# 3PhaseMeter.net
KiCad netlist of a schematic drawn in Altium Designer
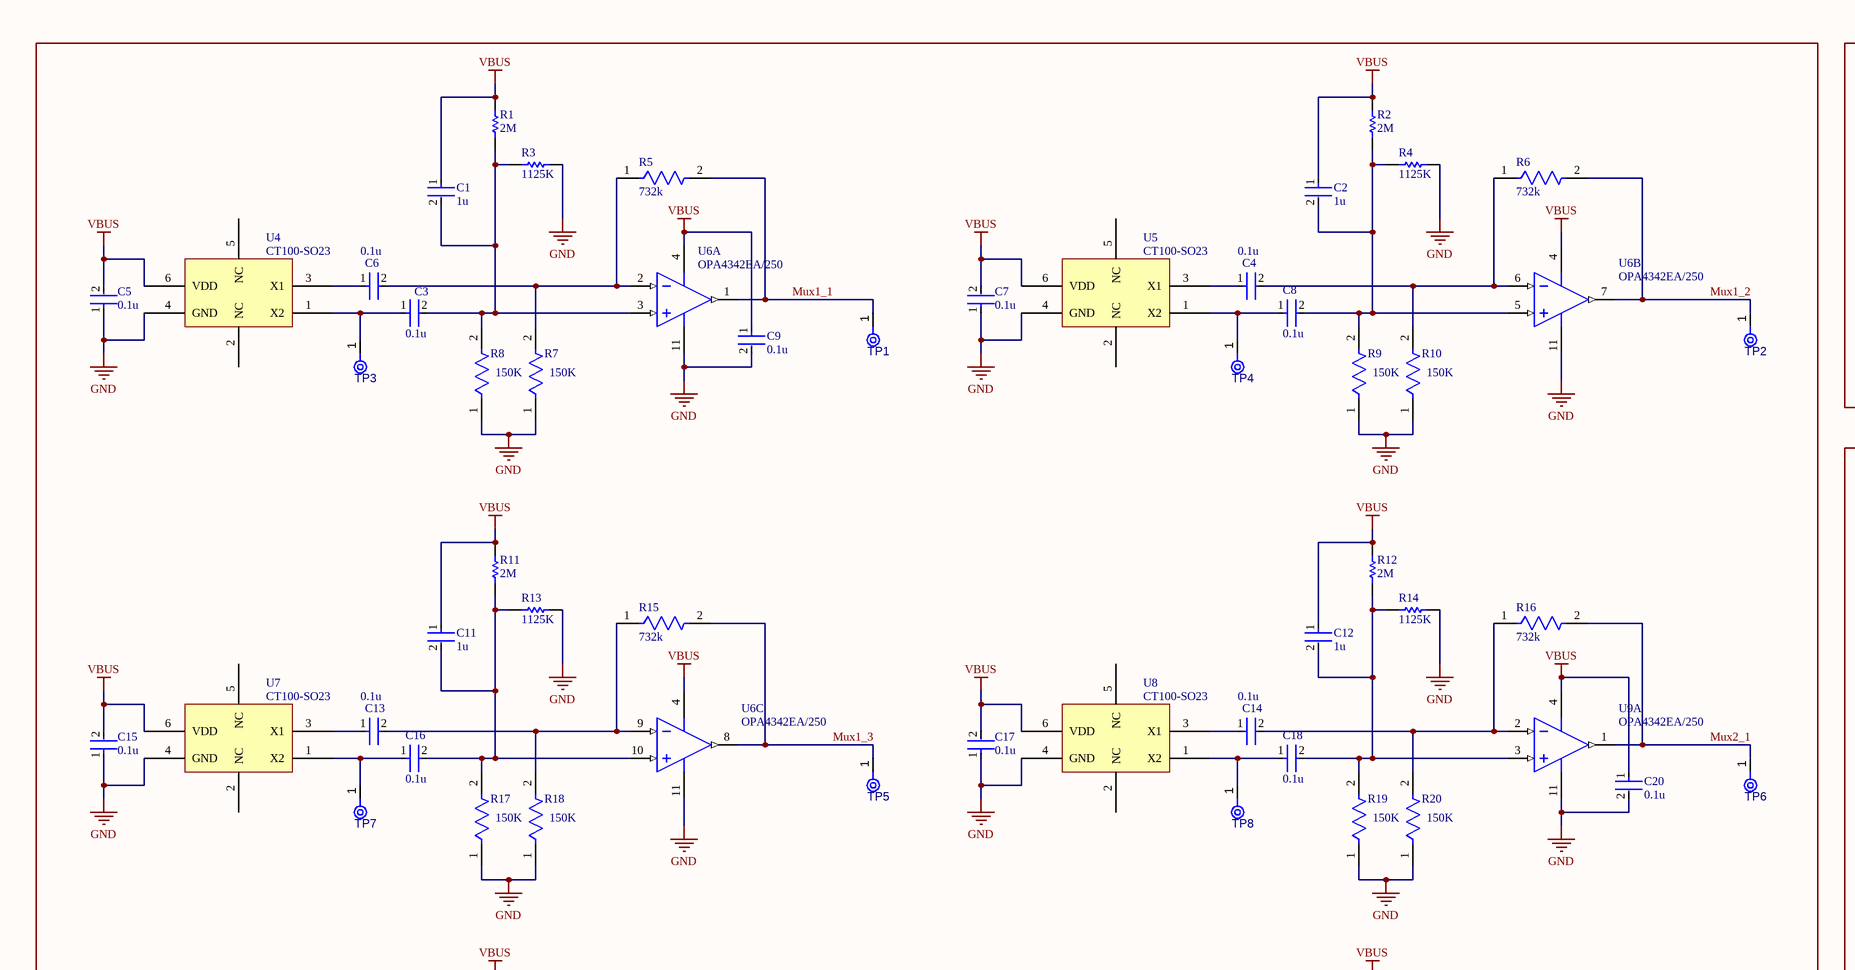
[diagram p0: 3PhaseMeter.SchDoc, top left]
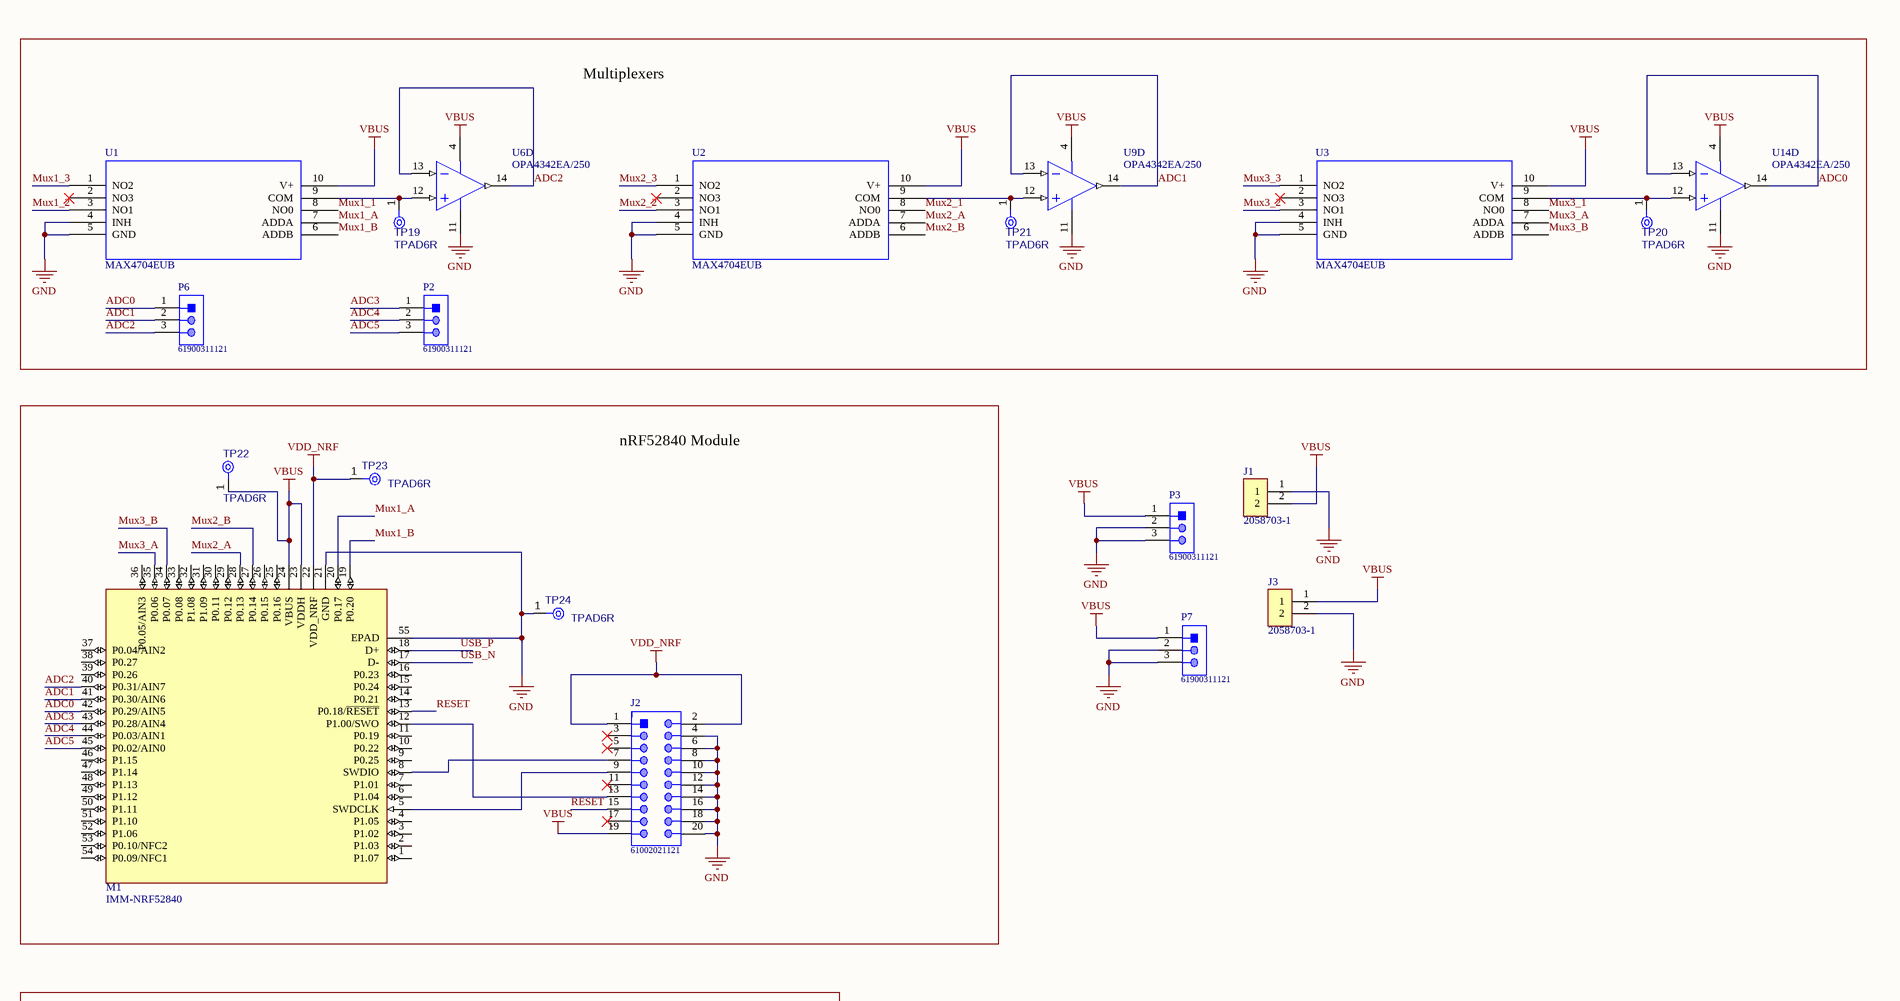
[diagram p1: 3PhaseMeter.SchDoc, top right]
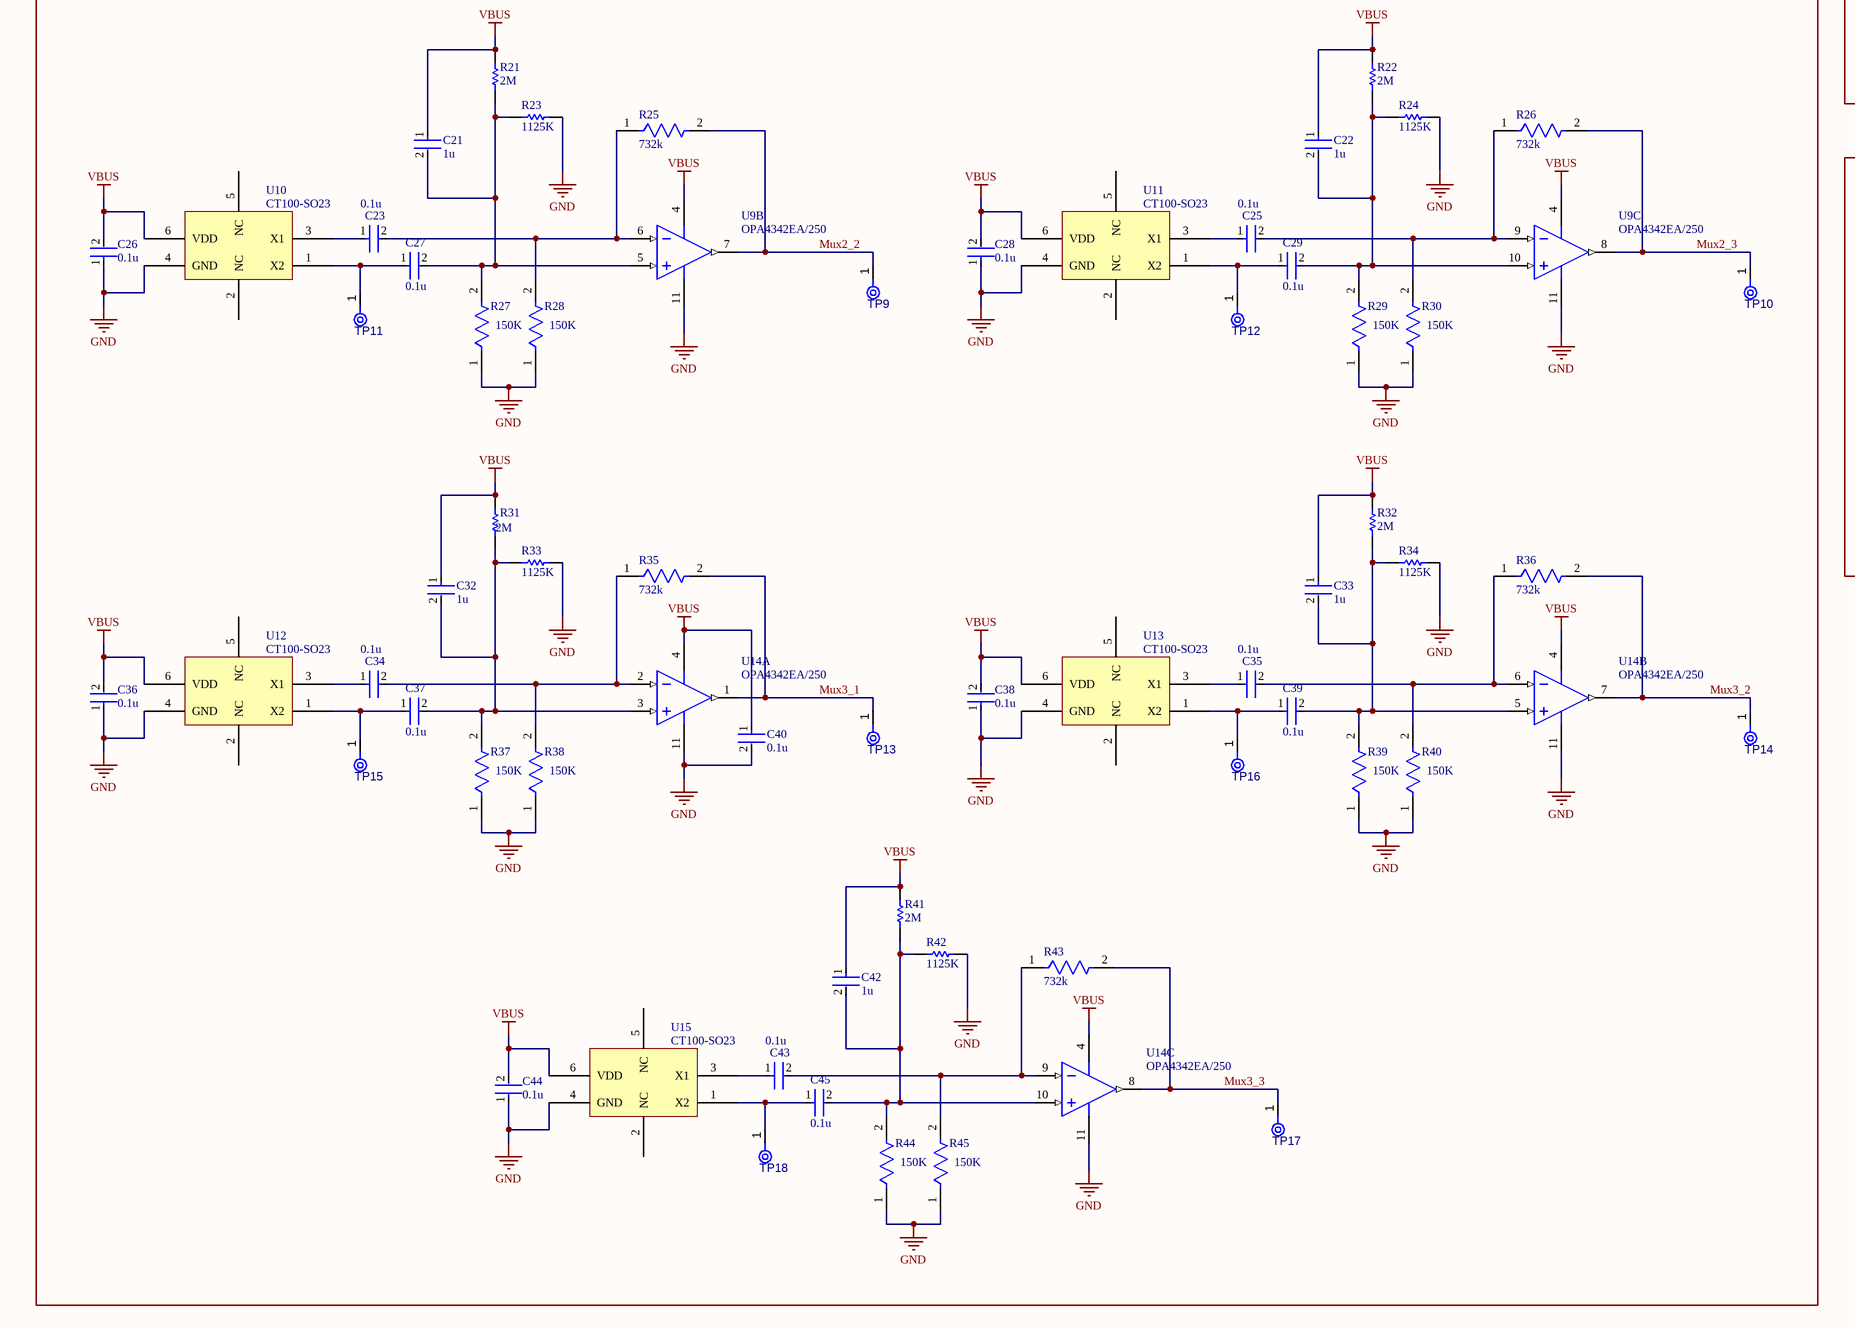
[diagram p2: 3PhaseMeter.SchDoc, bottom left]
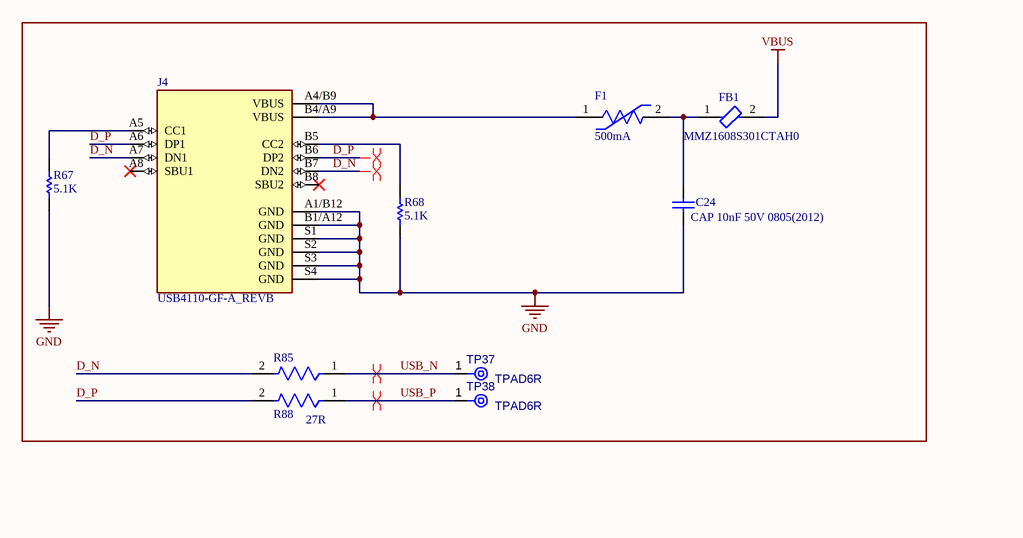
[diagram p3: 3PhaseMeter.SchDoc, bottom right]

(export (version "E")
  (design (tool "Eeschema 10.0.6"))
  (components
    (comp (ref "C1")
      (value "1u")
      (footprint "FP-C3216-160-0_2-IPC_C")
      (description "Multilayer Ceramic Capacitors 1uF ±10% 50V X8R SMD 1206")
      (fields (field (name "TOLERANCE") "10%"))
      (libsource (lib "Altium Content Vault") (part "11868f565c42a9108669ba33697ecf6"))
    )
    (comp (ref "C2")
      (value "1u")
      (footprint "FP-C3216-160-0_2-IPC_C")
      (description "Multilayer Ceramic Capacitors 1uF ±10% 50V X8R SMD 1206")
      (fields (field (name "TOLERANCE") "10%"))
      (libsource (lib "Altium Content Vault") (part "11868f565c42a9108669ba33697ecf6"))
    )
    (comp (ref "C3")
      (value "0.1u")
      (footprint "FP-C0805C-DN-MFG")
      (description "CAP CER 0.1UF 50V X7R 0805")
      (fields
        (field (name "MANUFACTURER PART NUMBER") "C0805C104K5RACTU")
        (field (name "MANUFACTURER") "KEMET")
      )
      (libsource (lib "Altium Content Vault") (part "b4654b650e69147ec39a6b967a45e02"))
    )
    (comp (ref "C4")
      (value "0.1u")
      (footprint "FP-C0805C-DN-MFG")
      (description "CAP CER 0.1UF 50V X7R 0805")
      (fields
        (field (name "MANUFACTURER PART NUMBER") "C0805C104K5RACTU")
        (field (name "MANUFACTURER") "KEMET")
      )
      (libsource (lib "Altium Content Vault") (part "b4654b650e69147ec39a6b967a45e02"))
    )
    (comp (ref "C5")
      (value "0.1u")
      (footprint "FP-C0805C-DN-MFG")
      (description "CAP CER 0.1UF 50V X7R 0805")
      (fields
        (field (name "MANUFACTURER PART NUMBER") "C0805C104K5RACTU")
        (field (name "MANUFACTURER") "KEMET")
      )
      (libsource (lib "Altium Content Vault") (part "b4654b650e69147ec39a6b967a45e02"))
    )
    (comp (ref "C6")
      (value "0.1u")
      (footprint "FP-C0805C-DN-MFG")
      (description "CAP CER 0.1UF 50V X7R 0805")
      (fields
        (field (name "MANUFACTURER PART NUMBER") "C0805C104K5RACTU")
        (field (name "MANUFACTURER") "KEMET")
      )
      (libsource (lib "Altium Content Vault") (part "b4654b650e69147ec39a6b967a45e02"))
    )
    (comp (ref "C7")
      (value "0.1u")
      (footprint "FP-C0805C-DN-MFG")
      (description "CAP CER 0.1UF 50V X7R 0805")
      (fields
        (field (name "MANUFACTURER PART NUMBER") "C0805C104K5RACTU")
        (field (name "MANUFACTURER") "KEMET")
      )
      (libsource (lib "Altium Content Vault") (part "b4654b650e69147ec39a6b967a45e02"))
    )
    (comp (ref "C8")
      (value "0.1u")
      (footprint "FP-C0805C-DN-MFG")
      (description "CAP CER 0.1UF 50V X7R 0805")
      (fields
        (field (name "MANUFACTURER PART NUMBER") "C0805C104K5RACTU")
        (field (name "MANUFACTURER") "KEMET")
      )
      (libsource (lib "Altium Content Vault") (part "b4654b650e69147ec39a6b967a45e02"))
    )
    (comp (ref "C9")
      (value "0.1u")
      (footprint "FP-1206-L_3_2_0_2-W_1_6_0-IPC_A")
      (description "General Purpose Ceramic Capacitor, 1206, 100nF, 5%, X7R, 15%, 50V")
      (fields (field (name "VOLTAGE") "50V") (field (name "TOLERANCE") "5%"))
      (libsource (lib "Altium Content Vault") (part "02cd4be3c70576c341d710602a673aa"))
    )
    (comp (ref "C11")
      (value "1u")
      (footprint "FP-C3216-160-0_2-IPC_C")
      (description "Multilayer Ceramic Capacitors 1uF ±10% 50V X8R SMD 1206")
      (fields (field (name "TOLERANCE") "10%"))
      (libsource (lib "Altium Content Vault") (part "11868f565c42a9108669ba33697ecf6"))
    )
    (comp (ref "C12")
      (value "1u")
      (footprint "FP-C3216-160-0_2-IPC_C")
      (description "Multilayer Ceramic Capacitors 1uF ±10% 50V X8R SMD 1206")
      (fields (field (name "TOLERANCE") "10%"))
      (libsource (lib "Altium Content Vault") (part "11868f565c42a9108669ba33697ecf6"))
    )
    (comp (ref "C13")
      (value "0.1u")
      (footprint "FP-C0805C-DN-MFG")
      (description "CAP CER 0.1UF 50V X7R 0805")
      (fields
        (field (name "MANUFACTURER PART NUMBER") "C0805C104K5RACTU")
        (field (name "MANUFACTURER") "KEMET")
      )
      (libsource (lib "Altium Content Vault") (part "b4654b650e69147ec39a6b967a45e02"))
    )
    (comp (ref "C14")
      (value "0.1u")
      (footprint "FP-C0805C-DN-MFG")
      (description "CAP CER 0.1UF 50V X7R 0805")
      (fields
        (field (name "MANUFACTURER PART NUMBER") "C0805C104K5RACTU")
        (field (name "MANUFACTURER") "KEMET")
      )
      (libsource (lib "Altium Content Vault") (part "b4654b650e69147ec39a6b967a45e02"))
    )
    (comp (ref "C15")
      (value "0.1u")
      (footprint "FP-C0805C-DN-MFG")
      (description "CAP CER 0.1UF 50V X7R 0805")
      (fields
        (field (name "MANUFACTURER PART NUMBER") "C0805C104K5RACTU")
        (field (name "MANUFACTURER") "KEMET")
      )
      (libsource (lib "Altium Content Vault") (part "b4654b650e69147ec39a6b967a45e02"))
    )
    (comp (ref "C16")
      (value "0.1u")
      (footprint "FP-C0805C-DN-MFG")
      (description "CAP CER 0.1UF 50V X7R 0805")
      (fields
        (field (name "MANUFACTURER PART NUMBER") "C0805C104K5RACTU")
        (field (name "MANUFACTURER") "KEMET")
      )
      (libsource (lib "Altium Content Vault") (part "b4654b650e69147ec39a6b967a45e02"))
    )
    (comp (ref "C17")
      (value "0.1u")
      (footprint "FP-C0805C-DN-MFG")
      (description "CAP CER 0.1UF 50V X7R 0805")
      (fields
        (field (name "MANUFACTURER PART NUMBER") "C0805C104K5RACTU")
        (field (name "MANUFACTURER") "KEMET")
      )
      (libsource (lib "Altium Content Vault") (part "b4654b650e69147ec39a6b967a45e02"))
    )
    (comp (ref "C18")
      (value "0.1u")
      (footprint "FP-C0805C-DN-MFG")
      (description "CAP CER 0.1UF 50V X7R 0805")
      (fields
        (field (name "MANUFACTURER PART NUMBER") "C0805C104K5RACTU")
        (field (name "MANUFACTURER") "KEMET")
      )
      (libsource (lib "Altium Content Vault") (part "b4654b650e69147ec39a6b967a45e02"))
    )
    (comp (ref "C20")
      (value "0.1u")
      (footprint "FP-1206-L_3_2_0_2-W_1_6_0-IPC_A")
      (description "General Purpose Ceramic Capacitor, 1206, 100nF, 5%, X7R, 15%, 50V")
      (fields (field (name "VOLTAGE") "50V") (field (name "TOLERANCE") "5%"))
      (libsource (lib "Altium Content Vault") (part "02cd4be3c70576c341d710602a673aa"))
    )
    (comp (ref "C21")
      (value "1u")
      (footprint "FP-C3216-160-0_2-IPC_C")
      (description "Multilayer Ceramic Capacitors 1uF ±10% 50V X8R SMD 1206")
      (fields (field (name "TOLERANCE") "10%"))
      (libsource (lib "Altium Content Vault") (part "11868f565c42a9108669ba33697ecf6"))
    )
    (comp (ref "C22")
      (value "1u")
      (footprint "FP-C3216-160-0_2-IPC_C")
      (description "Multilayer Ceramic Capacitors 1uF ±10% 50V X8R SMD 1206")
      (fields (field (name "TOLERANCE") "10%"))
      (libsource (lib "Altium Content Vault") (part "11868f565c42a9108669ba33697ecf6"))
    )
    (comp (ref "C23")
      (value "0.1u")
      (footprint "FP-C0805C-DN-MFG")
      (description "CAP CER 0.1UF 50V X7R 0805")
      (fields
        (field (name "MANUFACTURER PART NUMBER") "C0805C104K5RACTU")
        (field (name "MANUFACTURER") "KEMET")
      )
      (libsource (lib "Altium Content Vault") (part "b4654b650e69147ec39a6b967a45e02"))
    )
    (comp (ref "C24")
      (value "CAP 10nF 50V 0805(2012)")
      (footprint "CAPC0805(2012)75_N")
      (description "CAP 10nF 50V ±5% 0805 (2012 Metric) Thickness 0.75mm SMD")
      (fields (field (name "TOLERANCE") "Â±5%"))
      (libsource (lib "Altium Content Vault") (part "CAP"))
    )
    (comp (ref "C25")
      (value "0.1u")
      (footprint "FP-C0805C-DN-MFG")
      (description "CAP CER 0.1UF 50V X7R 0805")
      (fields
        (field (name "MANUFACTURER PART NUMBER") "C0805C104K5RACTU")
        (field (name "MANUFACTURER") "KEMET")
      )
      (libsource (lib "Altium Content Vault") (part "b4654b650e69147ec39a6b967a45e02"))
    )
    (comp (ref "C26")
      (value "0.1u")
      (footprint "FP-C0805C-DN-MFG")
      (description "CAP CER 0.1UF 50V X7R 0805")
      (fields
        (field (name "MANUFACTURER PART NUMBER") "C0805C104K5RACTU")
        (field (name "MANUFACTURER") "KEMET")
      )
      (libsource (lib "Altium Content Vault") (part "b4654b650e69147ec39a6b967a45e02"))
    )
    (comp (ref "C27")
      (value "0.1u")
      (footprint "FP-C0805C-DN-MFG")
      (description "CAP CER 0.1UF 50V X7R 0805")
      (fields
        (field (name "MANUFACTURER PART NUMBER") "C0805C104K5RACTU")
        (field (name "MANUFACTURER") "KEMET")
      )
      (libsource (lib "Altium Content Vault") (part "b4654b650e69147ec39a6b967a45e02"))
    )
    (comp (ref "C28")
      (value "0.1u")
      (footprint "FP-C0805C-DN-MFG")
      (description "CAP CER 0.1UF 50V X7R 0805")
      (fields
        (field (name "MANUFACTURER PART NUMBER") "C0805C104K5RACTU")
        (field (name "MANUFACTURER") "KEMET")
      )
      (libsource (lib "Altium Content Vault") (part "b4654b650e69147ec39a6b967a45e02"))
    )
    (comp (ref "C29")
      (value "0.1u")
      (footprint "FP-C0805C-DN-MFG")
      (description "CAP CER 0.1UF 50V X7R 0805")
      (fields
        (field (name "MANUFACTURER PART NUMBER") "C0805C104K5RACTU")
        (field (name "MANUFACTURER") "KEMET")
      )
      (libsource (lib "Altium Content Vault") (part "b4654b650e69147ec39a6b967a45e02"))
    )
    (comp (ref "C32")
      (value "1u")
      (footprint "FP-C3216-160-0_2-IPC_C")
      (description "Multilayer Ceramic Capacitors 1uF ±10% 50V X8R SMD 1206")
      (fields (field (name "TOLERANCE") "10%"))
      (libsource (lib "Altium Content Vault") (part "11868f565c42a9108669ba33697ecf6"))
    )
    (comp (ref "C33")
      (value "1u")
      (footprint "FP-C3216-160-0_2-IPC_C")
      (description "Multilayer Ceramic Capacitors 1uF ±10% 50V X8R SMD 1206")
      (fields (field (name "TOLERANCE") "10%"))
      (libsource (lib "Altium Content Vault") (part "11868f565c42a9108669ba33697ecf6"))
    )
    (comp (ref "C34")
      (value "0.1u")
      (footprint "FP-C0805C-DN-MFG")
      (description "CAP CER 0.1UF 50V X7R 0805")
      (fields
        (field (name "MANUFACTURER PART NUMBER") "C0805C104K5RACTU")
        (field (name "MANUFACTURER") "KEMET")
      )
      (libsource (lib "Altium Content Vault") (part "b4654b650e69147ec39a6b967a45e02"))
    )
    (comp (ref "C35")
      (value "0.1u")
      (footprint "FP-C0805C-DN-MFG")
      (description "CAP CER 0.1UF 50V X7R 0805")
      (fields
        (field (name "MANUFACTURER PART NUMBER") "C0805C104K5RACTU")
        (field (name "MANUFACTURER") "KEMET")
      )
      (libsource (lib "Altium Content Vault") (part "b4654b650e69147ec39a6b967a45e02"))
    )
    (comp (ref "C36")
      (value "0.1u")
      (footprint "FP-C0805C-DN-MFG")
      (description "CAP CER 0.1UF 50V X7R 0805")
      (fields
        (field (name "MANUFACTURER PART NUMBER") "C0805C104K5RACTU")
        (field (name "MANUFACTURER") "KEMET")
      )
      (libsource (lib "Altium Content Vault") (part "b4654b650e69147ec39a6b967a45e02"))
    )
    (comp (ref "C37")
      (value "0.1u")
      (footprint "FP-C0805C-DN-MFG")
      (description "CAP CER 0.1UF 50V X7R 0805")
      (fields
        (field (name "MANUFACTURER PART NUMBER") "C0805C104K5RACTU")
        (field (name "MANUFACTURER") "KEMET")
      )
      (libsource (lib "Altium Content Vault") (part "b4654b650e69147ec39a6b967a45e02"))
    )
    (comp (ref "C38")
      (value "0.1u")
      (footprint "FP-C0805C-DN-MFG")
      (description "CAP CER 0.1UF 50V X7R 0805")
      (fields
        (field (name "MANUFACTURER PART NUMBER") "C0805C104K5RACTU")
        (field (name "MANUFACTURER") "KEMET")
      )
      (libsource (lib "Altium Content Vault") (part "b4654b650e69147ec39a6b967a45e02"))
    )
    (comp (ref "C39")
      (value "0.1u")
      (footprint "FP-C0805C-DN-MFG")
      (description "CAP CER 0.1UF 50V X7R 0805")
      (fields
        (field (name "MANUFACTURER PART NUMBER") "C0805C104K5RACTU")
        (field (name "MANUFACTURER") "KEMET")
      )
      (libsource (lib "Altium Content Vault") (part "b4654b650e69147ec39a6b967a45e02"))
    )
    (comp (ref "C40")
      (value "0.1u")
      (footprint "FP-1206-L_3_2_0_2-W_1_6_0-IPC_A")
      (description "General Purpose Ceramic Capacitor, 1206, 100nF, 5%, X7R, 15%, 50V")
      (fields (field (name "VOLTAGE") "50V") (field (name "TOLERANCE") "5%"))
      (libsource (lib "Altium Content Vault") (part "02cd4be3c70576c341d710602a673aa"))
    )
    (comp (ref "C42")
      (value "1u")
      (footprint "FP-C3216-160-0_2-IPC_C")
      (description "Multilayer Ceramic Capacitors 1uF ±10% 50V X8R SMD 1206")
      (fields (field (name "TOLERANCE") "10%"))
      (libsource (lib "Altium Content Vault") (part "11868f565c42a9108669ba33697ecf6"))
    )
    (comp (ref "C43")
      (value "0.1u")
      (footprint "FP-C0805C-DN-MFG")
      (description "CAP CER 0.1UF 50V X7R 0805")
      (fields
        (field (name "MANUFACTURER PART NUMBER") "C0805C104K5RACTU")
        (field (name "MANUFACTURER") "KEMET")
      )
      (libsource (lib "Altium Content Vault") (part "b4654b650e69147ec39a6b967a45e02"))
    )
    (comp (ref "C44")
      (value "0.1u")
      (footprint "FP-C0805C-DN-MFG")
      (description "CAP CER 0.1UF 50V X7R 0805")
      (fields
        (field (name "MANUFACTURER PART NUMBER") "C0805C104K5RACTU")
        (field (name "MANUFACTURER") "KEMET")
      )
      (libsource (lib "Altium Content Vault") (part "b4654b650e69147ec39a6b967a45e02"))
    )
    (comp (ref "C45")
      (value "0.1u")
      (footprint "FP-C0805C-DN-MFG")
      (description "CAP CER 0.1UF 50V X7R 0805")
      (fields
        (field (name "MANUFACTURER PART NUMBER") "C0805C104K5RACTU")
        (field (name "MANUFACTURER") "KEMET")
      )
      (libsource (lib "Altium Content Vault") (part "b4654b650e69147ec39a6b967a45e02"))
    )
    (comp (ref "F1")
      (value "500mA")
      (footprint "FP-1206L050YR-MFG")
      (description "PTC RESET FUSE 6V 500MA 1206")
      (libsource (lib "Altium Content Vault") (part "fdf083d5f6389a9a1c4e51137f46658"))
    )
    (comp (ref "FB1")
      (value "MMZ1608S301CTAH0")
      (footprint "FP-MMZ1608-0_6-IPC_C")
      (description "Signal Line Ferrite Bead 300 Ω 100MHz 500mA DCR 250mΩ SMD 0603")
      (fields (field (name "TOLERANCE") "25%"))
      (libsource (lib "Altium Content Vault") (part "5f30dd21d616792df468990f7003faa"))
    )
    (comp (ref "J1")
      (value "2058703-1")
      (footprint "TE_2058703-1")
      (description "CONN SSL RCPT & BLADE 2POS 4MM")
      (fields (field (name "MF") "{'manufacturer': u'TE Connectivity'}"))
      (libsource (lib "SnapEDA_Library") (part "2058703-1"))
    )
    (comp (ref "J2")
      (value "61002021121")
      (footprint "61002021121")
      (description "SMT Vertical Pin Header WR-PHD, Pitch 2.54 mm, Dual Row, 20 pins")
      (fields (field (name "MANUFACTURER") "Wurth Elektronik") (field (name "PUBLISHER") "WurthElektronik"))
      (libsource (lib "Altium Content Vault") (part "WE-CN-2P-M-R20"))
    )
    (comp (ref "J3")
      (value "2058703-1")
      (footprint "TE_2058703-1")
      (description "CONN SSL RCPT & BLADE 2POS 4MM")
      (fields (field (name "MF") "{'manufacturer': u'TE Connectivity'}"))
      (libsource (lib "SnapEDA_Library") (part "2058703-1"))
    )
    (comp (ref "J4")
      (value "USB4110-GF-A_REVB")
      (footprint "USB4110-GF-A:GCT_USB4110-GF-A_REVB")
      (fields (field (name "MF") "{'manufacturer': u'GCT'}"))
      (libsource (lib "*") (part "USB4110-GF-A_REVB"))
    )
    (comp (ref "M1")
      (value "IMM-NRF52840")
      (footprint "IMM-NRF52840")
      (description "IMM-NRF52840 - ANT+ & BLE module")
      (libsource (lib "IMM-NRF5x") (part "IMM-NRF52840"))
    )
    (comp (ref "P2")
      (value "61900311121")
      (footprint "61900311121")
      (description "Male Locking Header WR-WTB, THT, Vertical, pitch 2.54 mm, 1 x 3 position")
      (fields (field (name "MANUFACTURER") "Wurth Elektronik") (field (name "PUBLISHER") "WurthElektronik"))
      (libsource (lib "Altium Content Vault") (part "WE-CN-1P-M-R3"))
    )
    (comp (ref "P3")
      (value "61900311121")
      (footprint "61900311121")
      (description "Male Locking Header WR-WTB, THT, Vertical, pitch 2.54 mm, 1 x 3 position")
      (fields (field (name "MANUFACTURER") "Wurth Elektronik") (field (name "PUBLISHER") "WurthElektronik"))
      (libsource (lib "Altium Content Vault") (part "WE-CN-1P-M-R3"))
    )
    (comp (ref "P6")
      (value "61900311121")
      (footprint "61900311121")
      (description "Male Locking Header WR-WTB, THT, Vertical, pitch 2.54 mm, 1 x 3 position")
      (fields (field (name "MANUFACTURER") "Wurth Elektronik") (field (name "PUBLISHER") "WurthElektronik"))
      (libsource (lib "Altium Content Vault") (part "WE-CN-1P-M-R3"))
    )
    (comp (ref "P7")
      (value "61900311121")
      (footprint "61900311121")
      (description "Male Locking Header WR-WTB, THT, Vertical, pitch 2.54 mm, 1 x 3 position")
      (fields (field (name "MANUFACTURER") "Wurth Elektronik") (field (name "PUBLISHER") "WurthElektronik"))
      (libsource (lib "Altium Content Vault") (part "WE-CN-1P-M-R3"))
    )
    (comp (ref "R1")
      (value "2M")
      (footprint "RESC2013X60X40LL20T25")
      (fields (field (name "PART NUMBER") "ERA6AEB204V") (field (name "MANUFACTURER") "Panasonic"))
      (libsource (lib "Altium Content Vault") (part "RES"))
    )
    (comp (ref "R2")
      (value "2M")
      (footprint "RESC2013X60X40LL20T25")
      (fields (field (name "PART NUMBER") "ERA6AEB204V") (field (name "MANUFACTURER") "Panasonic"))
      (libsource (lib "Altium Content Vault") (part "RES"))
    )
    (comp (ref "R3")
      (value "1125K")
      (footprint "RESC2013X60X35ML10T20")
      (description "Chip Resistor, 100 KOhm, +/- 1%, 0.125 W, -55 to 155 degC, 0805 (2012 Metric), RoHS, Tape and Reel")
      (fields (field (name "MANUFACTURER") "Yageo") (field (name "TOLERANCE") "1%"))
      (libsource (lib "Altium Content Vault") (part "RES-2"))
    )
    (comp (ref "R4")
      (value "1125K")
      (footprint "RESC2013X60X35ML10T20")
      (description "Chip Resistor, 100 KOhm, +/- 1%, 0.125 W, -55 to 155 degC, 0805 (2012 Metric), RoHS, Tape and Reel")
      (fields (field (name "MANUFACTURER") "Yageo") (field (name "TOLERANCE") "1%"))
      (libsource (lib "Altium Content Vault") (part "RES-2"))
    )
    (comp (ref "R5")
      (value "732k")
      (footprint "FP-AC0805-MFG")
      (description "Res Thick Film 0805 100K Ohm 1% 1/8W ±100ppm/°C Molded SMD SMD Paper T/R")
      (fields
        (field (name "OCTOPART") "https://octopart.com/ac0805fr-07100kl-yageo-24517275")
        (field (name "MANUFACTURER") "Yageo")
      )
      (libsource (lib "Altium Content Vault") (part "1029c3af85768c4190bb7ad29bc67b5"))
    )
    (comp (ref "R6")
      (value "732k")
      (footprint "FP-AC0805-MFG")
      (description "Res Thick Film 0805 100K Ohm 1% 1/8W ±100ppm/°C Molded SMD SMD Paper T/R")
      (fields
        (field (name "OCTOPART") "https://octopart.com/ac0805fr-07100kl-yageo-24517275")
        (field (name "MANUFACTURER") "Yageo")
      )
      (libsource (lib "Altium Content Vault") (part "1029c3af85768c4190bb7ad29bc67b5"))
    )
    (comp (ref "R7")
      (value "150K")
      (footprint "FP-CRCW0805-e3-MFG")
      (description "RES Thick Film, 150kΩ, 1%, 0.125W, 100ppm/°C, 0805")
      (fields (field (name "TOLERANCE") "1%"))
      (libsource (lib "Altium Content Vault") (part "1029c3af85768c4190bb7ad29bc67b5"))
    )
    (comp (ref "R8")
      (value "150K")
      (footprint "FP-CRCW0805-e3-MFG")
      (description "RES Thick Film, 150kΩ, 1%, 0.125W, 100ppm/°C, 0805")
      (fields (field (name "TOLERANCE") "1%"))
      (libsource (lib "Altium Content Vault") (part "1029c3af85768c4190bb7ad29bc67b5"))
    )
    (comp (ref "R9")
      (value "150K")
      (footprint "FP-CRCW0805-e3-MFG")
      (description "RES Thick Film, 150kΩ, 1%, 0.125W, 100ppm/°C, 0805")
      (fields (field (name "TOLERANCE") "1%"))
      (libsource (lib "Altium Content Vault") (part "1029c3af85768c4190bb7ad29bc67b5"))
    )
    (comp (ref "R10")
      (value "150K")
      (footprint "FP-CRCW0805-e3-MFG")
      (description "RES Thick Film, 150kΩ, 1%, 0.125W, 100ppm/°C, 0805")
      (fields (field (name "TOLERANCE") "1%"))
      (libsource (lib "Altium Content Vault") (part "1029c3af85768c4190bb7ad29bc67b5"))
    )
    (comp (ref "R11")
      (value "2M")
      (footprint "RESC2013X60X40LL20T25")
      (fields (field (name "PART NUMBER") "ERA6AEB204V") (field (name "MANUFACTURER") "Panasonic"))
      (libsource (lib "Altium Content Vault") (part "RES"))
    )
    (comp (ref "R12")
      (value "2M")
      (footprint "RESC2013X60X40LL20T25")
      (fields (field (name "PART NUMBER") "ERA6AEB204V") (field (name "MANUFACTURER") "Panasonic"))
      (libsource (lib "Altium Content Vault") (part "RES"))
    )
    (comp (ref "R13")
      (value "1125K")
      (footprint "RESC2013X60X35ML10T20")
      (description "Chip Resistor, 100 KOhm, +/- 1%, 0.125 W, -55 to 155 degC, 0805 (2012 Metric), RoHS, Tape and Reel")
      (fields (field (name "MANUFACTURER") "Yageo") (field (name "TOLERANCE") "1%"))
      (libsource (lib "Altium Content Vault") (part "RES-2"))
    )
    (comp (ref "R14")
      (value "1125K")
      (footprint "RESC2013X60X35ML10T20")
      (description "Chip Resistor, 100 KOhm, +/- 1%, 0.125 W, -55 to 155 degC, 0805 (2012 Metric), RoHS, Tape and Reel")
      (fields (field (name "MANUFACTURER") "Yageo") (field (name "TOLERANCE") "1%"))
      (libsource (lib "Altium Content Vault") (part "RES-2"))
    )
    (comp (ref "R15")
      (value "732k")
      (footprint "FP-AC0805-MFG")
      (description "Res Thick Film 0805 100K Ohm 1% 1/8W ±100ppm/°C Molded SMD SMD Paper T/R")
      (fields
        (field (name "OCTOPART") "https://octopart.com/ac0805fr-07100kl-yageo-24517275")
        (field (name "MANUFACTURER") "Yageo")
      )
      (libsource (lib "Altium Content Vault") (part "1029c3af85768c4190bb7ad29bc67b5"))
    )
    (comp (ref "R16")
      (value "732k")
      (footprint "FP-AC0805-MFG")
      (description "Res Thick Film 0805 100K Ohm 1% 1/8W ±100ppm/°C Molded SMD SMD Paper T/R")
      (fields
        (field (name "OCTOPART") "https://octopart.com/ac0805fr-07100kl-yageo-24517275")
        (field (name "MANUFACTURER") "Yageo")
      )
      (libsource (lib "Altium Content Vault") (part "1029c3af85768c4190bb7ad29bc67b5"))
    )
    (comp (ref "R17")
      (value "150K")
      (footprint "FP-CRCW0805-e3-MFG")
      (description "RES Thick Film, 150kΩ, 1%, 0.125W, 100ppm/°C, 0805")
      (fields (field (name "TOLERANCE") "1%"))
      (libsource (lib "Altium Content Vault") (part "1029c3af85768c4190bb7ad29bc67b5"))
    )
    (comp (ref "R18")
      (value "150K")
      (footprint "FP-CRCW0805-e3-MFG")
      (description "RES Thick Film, 150kΩ, 1%, 0.125W, 100ppm/°C, 0805")
      (fields (field (name "TOLERANCE") "1%"))
      (libsource (lib "Altium Content Vault") (part "1029c3af85768c4190bb7ad29bc67b5"))
    )
    (comp (ref "R19")
      (value "150K")
      (footprint "FP-CRCW0805-e3-MFG")
      (description "RES Thick Film, 150kΩ, 1%, 0.125W, 100ppm/°C, 0805")
      (fields (field (name "TOLERANCE") "1%"))
      (libsource (lib "Altium Content Vault") (part "1029c3af85768c4190bb7ad29bc67b5"))
    )
    (comp (ref "R20")
      (value "150K")
      (footprint "FP-CRCW0805-e3-MFG")
      (description "RES Thick Film, 150kΩ, 1%, 0.125W, 100ppm/°C, 0805")
      (fields (field (name "TOLERANCE") "1%"))
      (libsource (lib "Altium Content Vault") (part "1029c3af85768c4190bb7ad29bc67b5"))
    )
    (comp (ref "R21")
      (value "2M")
      (footprint "RESC2013X60X40LL20T25")
      (fields (field (name "PART NUMBER") "ERA6AEB204V") (field (name "MANUFACTURER") "Panasonic"))
      (libsource (lib "Altium Content Vault") (part "RES"))
    )
    (comp (ref "R22")
      (value "2M")
      (footprint "RESC2013X60X40LL20T25")
      (fields (field (name "PART NUMBER") "ERA6AEB204V") (field (name "MANUFACTURER") "Panasonic"))
      (libsource (lib "Altium Content Vault") (part "RES"))
    )
    (comp (ref "R23")
      (value "1125K")
      (footprint "RESC2013X60X35ML10T20")
      (description "Chip Resistor, 100 KOhm, +/- 1%, 0.125 W, -55 to 155 degC, 0805 (2012 Metric), RoHS, Tape and Reel")
      (fields (field (name "MANUFACTURER") "Yageo") (field (name "TOLERANCE") "1%"))
      (libsource (lib "Altium Content Vault") (part "RES-2"))
    )
    (comp (ref "R24")
      (value "1125K")
      (footprint "RESC2013X60X35ML10T20")
      (description "Chip Resistor, 100 KOhm, +/- 1%, 0.125 W, -55 to 155 degC, 0805 (2012 Metric), RoHS, Tape and Reel")
      (fields (field (name "MANUFACTURER") "Yageo") (field (name "TOLERANCE") "1%"))
      (libsource (lib "Altium Content Vault") (part "RES-2"))
    )
    (comp (ref "R25")
      (value "732k")
      (footprint "FP-AC0805-MFG")
      (description "Res Thick Film 0805 100K Ohm 1% 1/8W ±100ppm/°C Molded SMD SMD Paper T/R")
      (fields
        (field (name "OCTOPART") "https://octopart.com/ac0805fr-07100kl-yageo-24517275")
        (field (name "MANUFACTURER") "Yageo")
      )
      (libsource (lib "Altium Content Vault") (part "1029c3af85768c4190bb7ad29bc67b5"))
    )
    (comp (ref "R26")
      (value "732k")
      (footprint "FP-AC0805-MFG")
      (description "Res Thick Film 0805 100K Ohm 1% 1/8W ±100ppm/°C Molded SMD SMD Paper T/R")
      (fields
        (field (name "OCTOPART") "https://octopart.com/ac0805fr-07100kl-yageo-24517275")
        (field (name "MANUFACTURER") "Yageo")
      )
      (libsource (lib "Altium Content Vault") (part "1029c3af85768c4190bb7ad29bc67b5"))
    )
    (comp (ref "R27")
      (value "150K")
      (footprint "FP-CRCW0805-e3-MFG")
      (description "RES Thick Film, 150kΩ, 1%, 0.125W, 100ppm/°C, 0805")
      (fields (field (name "TOLERANCE") "1%"))
      (libsource (lib "Altium Content Vault") (part "1029c3af85768c4190bb7ad29bc67b5"))
    )
    (comp (ref "R28")
      (value "150K")
      (footprint "FP-CRCW0805-e3-MFG")
      (description "RES Thick Film, 150kΩ, 1%, 0.125W, 100ppm/°C, 0805")
      (fields (field (name "TOLERANCE") "1%"))
      (libsource (lib "Altium Content Vault") (part "1029c3af85768c4190bb7ad29bc67b5"))
    )
    (comp (ref "R29")
      (value "150K")
      (footprint "FP-CRCW0805-e3-MFG")
      (description "RES Thick Film, 150kΩ, 1%, 0.125W, 100ppm/°C, 0805")
      (fields (field (name "TOLERANCE") "1%"))
      (libsource (lib "Altium Content Vault") (part "1029c3af85768c4190bb7ad29bc67b5"))
    )
    (comp (ref "R30")
      (value "150K")
      (footprint "FP-CRCW0805-e3-MFG")
      (description "RES Thick Film, 150kΩ, 1%, 0.125W, 100ppm/°C, 0805")
      (fields (field (name "TOLERANCE") "1%"))
      (libsource (lib "Altium Content Vault") (part "1029c3af85768c4190bb7ad29bc67b5"))
    )
    (comp (ref "R31")
      (value "2M")
      (footprint "RESC2013X60X40LL20T25")
      (fields (field (name "PART NUMBER") "ERA6AEB204V") (field (name "MANUFACTURER") "Panasonic"))
      (libsource (lib "Altium Content Vault") (part "RES"))
    )
    (comp (ref "R32")
      (value "2M")
      (footprint "RESC2013X60X40LL20T25")
      (fields (field (name "PART NUMBER") "ERA6AEB204V") (field (name "MANUFACTURER") "Panasonic"))
      (libsource (lib "Altium Content Vault") (part "RES"))
    )
    (comp (ref "R33")
      (value "1125K")
      (footprint "RESC2013X60X35ML10T20")
      (description "Chip Resistor, 100 KOhm, +/- 1%, 0.125 W, -55 to 155 degC, 0805 (2012 Metric), RoHS, Tape and Reel")
      (fields (field (name "MANUFACTURER") "Yageo") (field (name "TOLERANCE") "1%"))
      (libsource (lib "Altium Content Vault") (part "RES-2"))
    )
    (comp (ref "R34")
      (value "1125K")
      (footprint "RESC2013X60X35ML10T20")
      (description "Chip Resistor, 100 KOhm, +/- 1%, 0.125 W, -55 to 155 degC, 0805 (2012 Metric), RoHS, Tape and Reel")
      (fields (field (name "MANUFACTURER") "Yageo") (field (name "TOLERANCE") "1%"))
      (libsource (lib "Altium Content Vault") (part "RES-2"))
    )
    (comp (ref "R35")
      (value "732k")
      (footprint "FP-AC0805-MFG")
      (description "Res Thick Film 0805 100K Ohm 1% 1/8W ±100ppm/°C Molded SMD SMD Paper T/R")
      (fields
        (field (name "OCTOPART") "https://octopart.com/ac0805fr-07100kl-yageo-24517275")
        (field (name "MANUFACTURER") "Yageo")
      )
      (libsource (lib "Altium Content Vault") (part "1029c3af85768c4190bb7ad29bc67b5"))
    )
    (comp (ref "R36")
      (value "732k")
      (footprint "FP-AC0805-MFG")
      (description "Res Thick Film 0805 100K Ohm 1% 1/8W ±100ppm/°C Molded SMD SMD Paper T/R")
      (fields
        (field (name "OCTOPART") "https://octopart.com/ac0805fr-07100kl-yageo-24517275")
        (field (name "MANUFACTURER") "Yageo")
      )
      (libsource (lib "Altium Content Vault") (part "1029c3af85768c4190bb7ad29bc67b5"))
    )
    (comp (ref "R37")
      (value "150K")
      (footprint "FP-CRCW0805-e3-MFG")
      (description "RES Thick Film, 150kΩ, 1%, 0.125W, 100ppm/°C, 0805")
      (fields (field (name "TOLERANCE") "1%"))
      (libsource (lib "Altium Content Vault") (part "1029c3af85768c4190bb7ad29bc67b5"))
    )
    (comp (ref "R38")
      (value "150K")
      (footprint "FP-CRCW0805-e3-MFG")
      (description "RES Thick Film, 150kΩ, 1%, 0.125W, 100ppm/°C, 0805")
      (fields (field (name "TOLERANCE") "1%"))
      (libsource (lib "Altium Content Vault") (part "1029c3af85768c4190bb7ad29bc67b5"))
    )
    (comp (ref "R39")
      (value "150K")
      (footprint "FP-CRCW0805-e3-MFG")
      (description "RES Thick Film, 150kΩ, 1%, 0.125W, 100ppm/°C, 0805")
      (fields (field (name "TOLERANCE") "1%"))
      (libsource (lib "Altium Content Vault") (part "1029c3af85768c4190bb7ad29bc67b5"))
    )
    (comp (ref "R40")
      (value "150K")
      (footprint "FP-CRCW0805-e3-MFG")
      (description "RES Thick Film, 150kΩ, 1%, 0.125W, 100ppm/°C, 0805")
      (fields (field (name "TOLERANCE") "1%"))
      (libsource (lib "Altium Content Vault") (part "1029c3af85768c4190bb7ad29bc67b5"))
    )
    (comp (ref "R41")
      (value "2M")
      (footprint "RESC2013X60X40LL20T25")
      (fields (field (name "PART NUMBER") "ERA6AEB204V") (field (name "MANUFACTURER") "Panasonic"))
      (libsource (lib "Altium Content Vault") (part "RES"))
    )
    (comp (ref "R42")
      (value "1125K")
      (footprint "RESC2013X60X35ML10T20")
      (description "Chip Resistor, 100 KOhm, +/- 1%, 0.125 W, -55 to 155 degC, 0805 (2012 Metric), RoHS, Tape and Reel")
      (fields (field (name "MANUFACTURER") "Yageo") (field (name "TOLERANCE") "1%"))
      (libsource (lib "Altium Content Vault") (part "RES-2"))
    )
    (comp (ref "R43")
      (value "732k")
      (footprint "FP-AC0805-MFG")
      (description "Res Thick Film 0805 100K Ohm 1% 1/8W ±100ppm/°C Molded SMD SMD Paper T/R")
      (fields
        (field (name "OCTOPART") "https://octopart.com/ac0805fr-07100kl-yageo-24517275")
        (field (name "MANUFACTURER") "Yageo")
      )
      (libsource (lib "Altium Content Vault") (part "1029c3af85768c4190bb7ad29bc67b5"))
    )
    (comp (ref "R44")
      (value "150K")
      (footprint "FP-CRCW0805-e3-MFG")
      (description "RES Thick Film, 150kΩ, 1%, 0.125W, 100ppm/°C, 0805")
      (fields (field (name "TOLERANCE") "1%"))
      (libsource (lib "Altium Content Vault") (part "1029c3af85768c4190bb7ad29bc67b5"))
    )
    (comp (ref "R45")
      (value "150K")
      (footprint "FP-CRCW0805-e3-MFG")
      (description "RES Thick Film, 150kΩ, 1%, 0.125W, 100ppm/°C, 0805")
      (fields (field (name "TOLERANCE") "1%"))
      (libsource (lib "Altium Content Vault") (part "1029c3af85768c4190bb7ad29bc67b5"))
    )
    (comp (ref "R67")
      (value "5.1K")
      (footprint "RESC2013X70X40LL20T20")
      (fields (field (name "PART NUMBER") "ERJ6ENF5101V") (field (name "MANUFACTURER") "Panasonic"))
      (libsource (lib "Altium Content Vault") (part "RES"))
    )
    (comp (ref "R68")
      (value "5.1K")
      (footprint "RESC2013X70X40LL20T20")
      (fields (field (name "PART NUMBER") "ERJ6ENF5101V") (field (name "MANUFACTURER") "Panasonic"))
      (libsource (lib "Altium Content Vault") (part "RES"))
    )
    (comp (ref "R85")
      (value "27R")
      (footprint "FP-CRCW0805-e3-IPC_B")
      (description "RES Thick Film, 27Ω, 1%, 0.125W, 100ppm/°C, 0805")
      (fields (field (name "TOLERANCE") "1%"))
      (libsource (lib "Altium Content Vault") (part "1029c3af85768c4190bb7ad29bc67b5"))
    )
    (comp (ref "R88")
      (value "CRCW080527R0FKEA")
      (footprint "FP-CRCW0805-e3-IPC_B")
      (description "RES Thick Film, 27Ω, 1%, 0.125W, 100ppm/°C, 0805")
      (fields (field (name "TOLERANCE") "1%"))
      (libsource (lib "Altium Content Vault") (part "1029c3af85768c4190bb7ad29bc67b5"))
    )
    (comp (ref "TP1")
      (value "TPAD6R")
      (footprint "TP06R")
      (description "0.6mm round")
      (libsource (lib "Irfaan's Workspace") (part "CMP-001-0001-4"))
    )
    (comp (ref "TP2")
      (value "TPAD6R")
      (footprint "TP06R")
      (description "0.6mm round")
      (libsource (lib "Irfaan's Workspace") (part "CMP-001-0001-4"))
    )
    (comp (ref "TP3")
      (value "TPAD6R")
      (footprint "TP06R")
      (description "0.6mm round")
      (libsource (lib "Irfaan's Workspace") (part "CMP-001-0001-4"))
    )
    (comp (ref "TP4")
      (value "TPAD6R")
      (footprint "TP06R")
      (description "0.6mm round")
      (libsource (lib "Irfaan's Workspace") (part "CMP-001-0001-4"))
    )
    (comp (ref "TP5")
      (value "TPAD6R")
      (footprint "TP06R")
      (description "0.6mm round")
      (libsource (lib "Irfaan's Workspace") (part "CMP-001-0001-4"))
    )
    (comp (ref "TP6")
      (value "TPAD6R")
      (footprint "TP06R")
      (description "0.6mm round")
      (libsource (lib "Irfaan's Workspace") (part "CMP-001-0001-4"))
    )
    (comp (ref "TP7")
      (value "TPAD6R")
      (footprint "TP06R")
      (description "0.6mm round")
      (libsource (lib "Irfaan's Workspace") (part "CMP-001-0001-4"))
    )
    (comp (ref "TP8")
      (value "TPAD6R")
      (footprint "TP06R")
      (description "0.6mm round")
      (libsource (lib "Irfaan's Workspace") (part "CMP-001-0001-4"))
    )
    (comp (ref "TP9")
      (value "TPAD6R")
      (footprint "TP06R")
      (description "0.6mm round")
      (libsource (lib "Irfaan's Workspace") (part "CMP-001-0001-4"))
    )
    (comp (ref "TP10")
      (value "TPAD6R")
      (footprint "TP06R")
      (description "0.6mm round")
      (libsource (lib "Irfaan's Workspace") (part "CMP-001-0001-4"))
    )
    (comp (ref "TP11")
      (value "TPAD6R")
      (footprint "TP06R")
      (description "0.6mm round")
      (libsource (lib "Irfaan's Workspace") (part "CMP-001-0001-4"))
    )
    (comp (ref "TP12")
      (value "TPAD6R")
      (footprint "TP06R")
      (description "0.6mm round")
      (libsource (lib "Irfaan's Workspace") (part "CMP-001-0001-4"))
    )
    (comp (ref "TP13")
      (value "TPAD6R")
      (footprint "TP06R")
      (description "0.6mm round")
      (libsource (lib "Irfaan's Workspace") (part "CMP-001-0001-4"))
    )
    (comp (ref "TP14")
      (value "TPAD6R")
      (footprint "TP06R")
      (description "0.6mm round")
      (libsource (lib "Irfaan's Workspace") (part "CMP-001-0001-4"))
    )
    (comp (ref "TP15")
      (value "TPAD6R")
      (footprint "TP06R")
      (description "0.6mm round")
      (libsource (lib "Irfaan's Workspace") (part "CMP-001-0001-4"))
    )
    (comp (ref "TP16")
      (value "TPAD6R")
      (footprint "TP06R")
      (description "0.6mm round")
      (libsource (lib "Irfaan's Workspace") (part "CMP-001-0001-4"))
    )
    (comp (ref "TP17")
      (value "TPAD6R")
      (footprint "TP06R")
      (description "0.6mm round")
      (libsource (lib "Irfaan's Workspace") (part "CMP-001-0001-4"))
    )
    (comp (ref "TP18")
      (value "TPAD6R")
      (footprint "TP06R")
      (description "0.6mm round")
      (libsource (lib "Irfaan's Workspace") (part "CMP-001-0001-4"))
    )
    (comp (ref "TP19")
      (value "TPAD6R")
      (footprint "TP06R")
      (description "0.6mm round")
      (libsource (lib "Irfaan's Workspace") (part "CMP-001-0001-4"))
    )
    (comp (ref "TP20")
      (value "TPAD6R")
      (footprint "TP06R")
      (description "0.6mm round")
      (libsource (lib "Irfaan's Workspace") (part "CMP-001-0001-4"))
    )
    (comp (ref "TP21")
      (value "TPAD6R")
      (footprint "TP06R")
      (description "0.6mm round")
      (libsource (lib "Irfaan's Workspace") (part "CMP-001-0001-4"))
    )
    (comp (ref "TP22")
      (value "TPAD6R")
      (footprint "TP06R")
      (description "0.6mm round")
      (libsource (lib "Irfaan's Workspace") (part "CMP-001-0001-4"))
    )
    (comp (ref "TP23")
      (value "TPAD6R")
      (footprint "TP06R")
      (description "0.6mm round")
      (libsource (lib "Irfaan's Workspace") (part "CMP-001-0001-4"))
    )
    (comp (ref "TP24")
      (value "TPAD6R")
      (footprint "TP06R")
      (description "0.6mm round")
      (libsource (lib "Irfaan's Workspace") (part "CMP-001-0001-4"))
    )
    (comp (ref "TP37")
      (value "TPAD6R")
      (footprint "TP06R")
      (description "0.6mm round")
      (libsource (lib "Irfaan's Workspace") (part "CMP-001-0001-4"))
    )
    (comp (ref "TP38")
      (value "TPAD6R")
      (footprint "TP06R")
      (description "0.6mm round")
      (libsource (lib "Irfaan's Workspace") (part "CMP-001-0001-4"))
    )
    (comp (ref "U1")
      (value "MAX4704EUB")
      (footprint "21-0061L")
      (fields (field (name "MF") "{'manufacturer': u'Maxim Integrated'}"))
      (libsource (lib "SnapEDA_Library") (part "MAX4704EUB"))
    )
    (comp (ref "U2")
      (value "MAX4704EUB")
      (footprint "21-0061L")
      (fields (field (name "MF") "{'manufacturer': u'Maxim Integrated'}"))
      (libsource (lib "SnapEDA_Library") (part "MAX4704EUB"))
    )
    (comp (ref "U3")
      (value "MAX4704EUB")
      (footprint "21-0061L")
      (fields (field (name "MF") "{'manufacturer': u'Maxim Integrated'}"))
      (libsource (lib "SnapEDA_Library") (part "MAX4704EUB"))
    )
    (comp (ref "U4")
      (value "CT100-SO23")
      (footprint "SOT95P280X135-6N")
      (description "TMR Sensor")
      (libsource (lib "Irfaan's Workspace") (part "CT100-SO23-Symbol-1"))
    )
    (comp (ref "U5")
      (value "CT100-SO23")
      (footprint "SOT95P280X135-6N")
      (description "TMR Sensor")
      (libsource (lib "Irfaan's Workspace") (part "CT100-SO23-Symbol-1"))
    )
    (comp (ref "U6")
      (value "OPA4342EA/250")
      (footprint "PW0014A_M")
      (fields (field (name "MANUFACTURER") "Texas Instruments"))
      (libsource (lib "Altium Content Vault") (part "TI-OPA16X4_4XXX-14"))
    )
    (comp (ref "U7")
      (value "CT100-SO23")
      (footprint "SOT95P280X135-6N")
      (description "TMR Sensor")
      (libsource (lib "Irfaan's Workspace") (part "CT100-SO23-Symbol-1"))
    )
    (comp (ref "U8")
      (value "CT100-SO23")
      (footprint "SOT95P280X135-6N")
      (description "TMR Sensor")
      (libsource (lib "Irfaan's Workspace") (part "CT100-SO23-Symbol-1"))
    )
    (comp (ref "U9")
      (value "OPA4342EA/250")
      (footprint "PW0014A_M")
      (fields (field (name "MANUFACTURER") "Texas Instruments"))
      (libsource (lib "Altium Content Vault") (part "TI-OPA16X4_4XXX-14"))
    )
    (comp (ref "U10")
      (value "CT100-SO23")
      (footprint "SOT95P280X135-6N")
      (description "TMR Sensor")
      (libsource (lib "Irfaan's Workspace") (part "CT100-SO23-Symbol-1"))
    )
    (comp (ref "U11")
      (value "CT100-SO23")
      (footprint "SOT95P280X135-6N")
      (description "TMR Sensor")
      (libsource (lib "Irfaan's Workspace") (part "CT100-SO23-Symbol-1"))
    )
    (comp (ref "U12")
      (value "CT100-SO23")
      (footprint "SOT95P280X135-6N")
      (description "TMR Sensor")
      (libsource (lib "Irfaan's Workspace") (part "CT100-SO23-Symbol-1"))
    )
    (comp (ref "U13")
      (value "CT100-SO23")
      (footprint "SOT95P280X135-6N")
      (description "TMR Sensor")
      (libsource (lib "Irfaan's Workspace") (part "CT100-SO23-Symbol-1"))
    )
    (comp (ref "U14")
      (value "OPA4342EA/250")
      (footprint "PW0014A_M")
      (fields (field (name "MANUFACTURER") "Texas Instruments"))
      (libsource (lib "Altium Content Vault") (part "TI-OPA16X4_4XXX-14"))
    )
    (comp (ref "U15")
      (value "CT100-SO23")
      (footprint "SOT95P280X135-6N")
      (description "TMR Sensor")
      (libsource (lib "Irfaan's Workspace") (part "CT100-SO23-Symbol-1"))
    )
  )
  (nets
    (net (code "1") (name "/ADC0") (class "Default")
      (node (ref "M1") (pin "42") (pinfunction "P0.29/AIN5_42") (pintype "bidirectional"))
      (node (ref "P6") (pin "1") (pinfunction "1_1") (pintype "passive"))
      (node (ref "U14") (pin "13") (pinfunction "IN_D-_13") (pintype "input"))
      (node (ref "U14") (pin "14") (pinfunction "OUT_D_14") (pintype "output"))
    )
    (net (code "2") (name "/ADC1") (class "Default")
      (node (ref "M1") (pin "41") (pinfunction "P0.30/AIN6_41") (pintype "bidirectional"))
      (node (ref "P6") (pin "2") (pinfunction "2_2") (pintype "passive"))
      (node (ref "U9") (pin "13") (pinfunction "IN_D-_13") (pintype "input"))
      (node (ref "U9") (pin "14") (pinfunction "OUT_D_14") (pintype "output"))
    )
    (net (code "3") (name "/ADC2") (class "Default")
      (node (ref "M1") (pin "40") (pinfunction "P0.31/AIN7_40") (pintype "bidirectional"))
      (node (ref "P6") (pin "3") (pinfunction "3_3") (pintype "passive"))
      (node (ref "U6") (pin "13") (pinfunction "IN_D-_13") (pintype "input"))
      (node (ref "U6") (pin "14") (pinfunction "OUT_D_14") (pintype "output"))
    )
    (net (code "4") (name "/ADC3") (class "Default")
      (node (ref "M1") (pin "43") (pinfunction "P0.28/AIN4_43") (pintype "bidirectional"))
      (node (ref "P2") (pin "1") (pinfunction "1_1") (pintype "passive"))
    )
    (net (code "5") (name "/ADC4") (class "Default")
      (node (ref "M1") (pin "44") (pinfunction "P0.03/AIN1_44") (pintype "bidirectional"))
      (node (ref "P2") (pin "2") (pinfunction "2_2") (pintype "passive"))
    )
    (net (code "6") (name "/ADC5") (class "Default")
      (node (ref "M1") (pin "45") (pinfunction "P0.02/AIN0_45") (pintype "bidirectional"))
      (node (ref "P2") (pin "3") (pinfunction "3_3") (pintype "passive"))
    )
    (net (code "7") (name "/D_N") (class "Default")
      (node (ref "J4") (pin "A7") (pinfunction "DN1_A7") (pintype "bidirectional"))
      (node (ref "J4") (pin "B7") (pinfunction "DN2_B7") (pintype "bidirectional"))
      (node (ref "R85") (pin "2") (pinfunction "2_2") (pintype "passive"))
    )
    (net (code "8") (name "/D_P") (class "Default")
      (node (ref "J4") (pin "A6") (pinfunction "DP1_A6") (pintype "bidirectional"))
      (node (ref "J4") (pin "B6") (pinfunction "DP2_B6") (pintype "bidirectional"))
      (node (ref "R88") (pin "2") (pinfunction "2_2") (pintype "passive"))
    )
    (net (code "9") (name "/Mux1_1") (class "Default")
      (node (ref "R5") (pin "2") (pinfunction "2_2") (pintype "passive"))
      (node (ref "TP1") (pin "1") (pinfunction "TP_1") (pintype "passive"))
      (node (ref "U1") (pin "8") (pinfunction "NO0_8") (pintype "passive"))
      (node (ref "U6") (pin "1") (pinfunction "OUT_A_1") (pintype "output"))
    )
    (net (code "10") (name "/Mux1_2") (class "Default")
      (node (ref "R6") (pin "2") (pinfunction "2_2") (pintype "passive"))
      (node (ref "TP2") (pin "1") (pinfunction "TP_1") (pintype "passive"))
      (node (ref "U1") (pin "3") (pinfunction "NO1_3") (pintype "passive"))
      (node (ref "U6") (pin "7") (pinfunction "OUT_B_7") (pintype "output"))
    )
    (net (code "11") (name "/Mux1_3") (class "Default")
      (node (ref "R15") (pin "2") (pinfunction "2_2") (pintype "passive"))
      (node (ref "TP5") (pin "1") (pinfunction "TP_1") (pintype "passive"))
      (node (ref "U1") (pin "1") (pinfunction "NO2_1") (pintype "passive"))
      (node (ref "U6") (pin "8") (pinfunction "OUT_C_8") (pintype "output"))
    )
    (net (code "12") (name "/Mux1_A") (class "Default")
      (node (ref "M1") (pin "20") (pinfunction "P0.17_20") (pintype "bidirectional"))
      (node (ref "U1") (pin "7") (pinfunction "ADDA_7") (pintype "passive"))
    )
    (net (code "13") (name "/Mux1_B") (class "Default")
      (node (ref "M1") (pin "19") (pinfunction "P0.20_19") (pintype "bidirectional"))
      (node (ref "U1") (pin "6") (pinfunction "ADDB_6") (pintype "passive"))
    )
    (net (code "14") (name "/Mux2_1") (class "Default")
      (node (ref "R16") (pin "2") (pinfunction "2_2") (pintype "passive"))
      (node (ref "TP6") (pin "1") (pinfunction "TP_1") (pintype "passive"))
      (node (ref "U2") (pin "8") (pinfunction "NO0_8") (pintype "passive"))
      (node (ref "U9") (pin "1") (pinfunction "OUT_A_1") (pintype "output"))
    )
    (net (code "15") (name "/Mux2_2") (class "Default")
      (node (ref "R25") (pin "2") (pinfunction "2_2") (pintype "passive"))
      (node (ref "TP9") (pin "1") (pinfunction "TP_1") (pintype "passive"))
      (node (ref "U2") (pin "3") (pinfunction "NO1_3") (pintype "passive"))
      (node (ref "U9") (pin "7") (pinfunction "OUT_B_7") (pintype "output"))
    )
    (net (code "16") (name "/Mux2_3") (class "Default")
      (node (ref "R26") (pin "2") (pinfunction "2_2") (pintype "passive"))
      (node (ref "TP10") (pin "1") (pinfunction "TP_1") (pintype "passive"))
      (node (ref "U2") (pin "1") (pinfunction "NO2_1") (pintype "passive"))
      (node (ref "U9") (pin "8") (pinfunction "OUT_C_8") (pintype "output"))
    )
    (net (code "17") (name "/Mux2_A") (class "Default")
      (node (ref "M1") (pin "28") (pinfunction "P0.13_28") (pintype "bidirectional"))
      (node (ref "U2") (pin "7") (pinfunction "ADDA_7") (pintype "passive"))
    )
    (net (code "18") (name "/Mux2_B") (class "Default")
      (node (ref "M1") (pin "27") (pinfunction "P0.14_27") (pintype "bidirectional"))
      (node (ref "U2") (pin "6") (pinfunction "ADDB_6") (pintype "passive"))
    )
    (net (code "19") (name "/Mux3_1") (class "Default")
      (node (ref "R35") (pin "2") (pinfunction "2_2") (pintype "passive"))
      (node (ref "TP13") (pin "1") (pinfunction "TP_1") (pintype "passive"))
      (node (ref "U14") (pin "1") (pinfunction "OUT_A_1") (pintype "output"))
      (node (ref "U3") (pin "8") (pinfunction "NO0_8") (pintype "passive"))
    )
    (net (code "20") (name "/Mux3_2") (class "Default")
      (node (ref "R36") (pin "2") (pinfunction "2_2") (pintype "passive"))
      (node (ref "TP14") (pin "1") (pinfunction "TP_1") (pintype "passive"))
      (node (ref "U14") (pin "7") (pinfunction "OUT_B_7") (pintype "output"))
      (node (ref "U3") (pin "3") (pinfunction "NO1_3") (pintype "passive"))
    )
    (net (code "21") (name "/Mux3_3") (class "Default")
      (node (ref "R43") (pin "2") (pinfunction "2_2") (pintype "passive"))
      (node (ref "TP17") (pin "1") (pinfunction "TP_1") (pintype "passive"))
      (node (ref "U14") (pin "8") (pinfunction "OUT_C_8") (pintype "output"))
      (node (ref "U3") (pin "1") (pinfunction "NO2_1") (pintype "passive"))
    )
    (net (code "22") (name "/Mux3_A") (class "Default")
      (node (ref "M1") (pin "35") (pinfunction "P0.06_35") (pintype "bidirectional"))
      (node (ref "U3") (pin "7") (pinfunction "ADDA_7") (pintype "passive"))
    )
    (net (code "23") (name "/Mux3_B") (class "Default")
      (node (ref "M1") (pin "34") (pinfunction "P0.07_34") (pintype "bidirectional"))
      (node (ref "U3") (pin "6") (pinfunction "ADDB_6") (pintype "passive"))
    )
    (net (code "24") (name "/RESET") (class "Default")
      (node (ref "J2") (pin "15") (pinfunction "15_15") (pintype "passive"))
      (node (ref "M1") (pin "13") (pinfunction "P0.18/~{RESET}_13") (pintype "bidirectional"))
    )
    (net (code "25") (name "/USB_N") (class "Default")
      (node (ref "M1") (pin "17") (pinfunction "D-_17") (pintype "bidirectional"))
      (node (ref "R85") (pin "1") (pinfunction "1_1") (pintype "passive"))
      (node (ref "TP37") (pin "1") (pinfunction "TP_1") (pintype "passive"))
    )
    (net (code "26") (name "/USB_P") (class "Default")
      (node (ref "M1") (pin "18") (pinfunction "D+_18") (pintype "bidirectional"))
      (node (ref "R88") (pin "1") (pinfunction "1_1") (pintype "passive"))
      (node (ref "TP38") (pin "1") (pinfunction "TP_1") (pintype "passive"))
    )
    (net (code "27") (name "GND") (class "Default")
      (node (ref "C15") (pin "1") (pinfunction "1_1") (pintype "passive"))
      (node (ref "C17") (pin "1") (pinfunction "1_1") (pintype "passive"))
      (node (ref "C20") (pin "2") (pinfunction "2_2") (pintype "passive"))
      (node (ref "C24") (pin "1") (pinfunction "1_1") (pintype "passive"))
      (node (ref "C26") (pin "1") (pinfunction "1_1") (pintype "passive"))
      (node (ref "C28") (pin "1") (pinfunction "1_1") (pintype "passive"))
      (node (ref "C36") (pin "1") (pinfunction "1_1") (pintype "passive"))
      (node (ref "C38") (pin "1") (pinfunction "1_1") (pintype "passive"))
      (node (ref "C40") (pin "2") (pinfunction "2_2") (pintype "passive"))
      (node (ref "C44") (pin "1") (pinfunction "1_1") (pintype "passive"))
      (node (ref "C5") (pin "1") (pinfunction "1_1") (pintype "passive"))
      (node (ref "C7") (pin "1") (pinfunction "1_1") (pintype "passive"))
      (node (ref "C9") (pin "2") (pinfunction "2_2") (pintype "passive"))
      (node (ref "J1") (pin "1") (pinfunction "1_1") (pintype "passive"))
      (node (ref "J2") (pin "10") (pinfunction "10_10") (pintype "passive"))
      (node (ref "J2") (pin "12") (pinfunction "12_12") (pintype "passive"))
      (node (ref "J2") (pin "14") (pinfunction "14_14") (pintype "passive"))
      (node (ref "J2") (pin "16") (pinfunction "16_16") (pintype "passive"))
      (node (ref "J2") (pin "18") (pinfunction "18_18") (pintype "passive"))
      (node (ref "J2") (pin "20") (pinfunction "20_20") (pintype "passive"))
      (node (ref "J2") (pin "4") (pinfunction "4_4") (pintype "passive"))
      (node (ref "J2") (pin "6") (pinfunction "6_6") (pintype "passive"))
      (node (ref "J2") (pin "8") (pinfunction "8_8") (pintype "passive"))
      (node (ref "J3") (pin "2") (pinfunction "2_2") (pintype "passive"))
      (node (ref "J4") (pin "A1/B12") (pinfunction "GND_A1/B12") (pintype "power_in"))
      (node (ref "J4") (pin "B1/A12") (pinfunction "GND_B1/A12") (pintype "power_in"))
      (node (ref "J4") (pin "S1") (pinfunction "GND_S1") (pintype "power_in"))
      (node (ref "J4") (pin "S2") (pinfunction "GND_S2") (pintype "power_in"))
      (node (ref "J4") (pin "S3") (pinfunction "GND_S3") (pintype "power_in"))
      (node (ref "J4") (pin "S4") (pinfunction "GND_S4") (pintype "power_in"))
      (node (ref "M1") (pin "21") (pinfunction "GND_21") (pintype "power_in"))
      (node (ref "M1") (pin "55") (pinfunction "EPAD_55") (pintype "passive"))
      (node (ref "P3") (pin "2") (pinfunction "2_2") (pintype "passive"))
      (node (ref "P3") (pin "3") (pinfunction "3_3") (pintype "passive"))
      (node (ref "P7") (pin "2") (pinfunction "2_2") (pintype "passive"))
      (node (ref "P7") (pin "3") (pinfunction "3_3") (pintype "passive"))
      (node (ref "R10") (pin "1") (pinfunction "1_1") (pintype "passive"))
      (node (ref "R13") (pin "2") (pinfunction "2_2") (pintype "passive"))
      (node (ref "R14") (pin "2") (pinfunction "2_2") (pintype "passive"))
      (node (ref "R17") (pin "1") (pinfunction "1_1") (pintype "passive"))
      (node (ref "R18") (pin "1") (pinfunction "1_1") (pintype "passive"))
      (node (ref "R19") (pin "1") (pinfunction "1_1") (pintype "passive"))
      (node (ref "R20") (pin "1") (pinfunction "1_1") (pintype "passive"))
      (node (ref "R23") (pin "2") (pinfunction "2_2") (pintype "passive"))
      (node (ref "R24") (pin "2") (pinfunction "2_2") (pintype "passive"))
      (node (ref "R27") (pin "1") (pinfunction "1_1") (pintype "passive"))
      (node (ref "R28") (pin "1") (pinfunction "1_1") (pintype "passive"))
      (node (ref "R29") (pin "1") (pinfunction "1_1") (pintype "passive"))
      (node (ref "R3") (pin "2") (pinfunction "2_2") (pintype "passive"))
      (node (ref "R30") (pin "1") (pinfunction "1_1") (pintype "passive"))
      (node (ref "R33") (pin "2") (pinfunction "2_2") (pintype "passive"))
      (node (ref "R34") (pin "2") (pinfunction "2_2") (pintype "passive"))
      (node (ref "R37") (pin "1") (pinfunction "1_1") (pintype "passive"))
      (node (ref "R38") (pin "1") (pinfunction "1_1") (pintype "passive"))
      (node (ref "R39") (pin "1") (pinfunction "1_1") (pintype "passive"))
      (node (ref "R4") (pin "2") (pinfunction "2_2") (pintype "passive"))
      (node (ref "R40") (pin "1") (pinfunction "1_1") (pintype "passive"))
      (node (ref "R42") (pin "2") (pinfunction "2_2") (pintype "passive"))
      (node (ref "R44") (pin "1") (pinfunction "1_1") (pintype "passive"))
      (node (ref "R45") (pin "1") (pinfunction "1_1") (pintype "passive"))
      (node (ref "R67") (pin "1") (pinfunction "1_1") (pintype "passive"))
      (node (ref "R68") (pin "1") (pinfunction "1_1") (pintype "passive"))
      (node (ref "R7") (pin "1") (pinfunction "1_1") (pintype "passive"))
      (node (ref "R8") (pin "1") (pinfunction "1_1") (pintype "passive"))
      (node (ref "R9") (pin "1") (pinfunction "1_1") (pintype "passive"))
      (node (ref "TP24") (pin "1") (pinfunction "TP_1") (pintype "passive"))
      (node (ref "U1") (pin "4") (pinfunction "INH_4") (pintype "passive"))
      (node (ref "U1") (pin "5") (pinfunction "GND_5") (pintype "power_in"))
      (node (ref "U10") (pin "4") (pinfunction "GND_4") (pintype "passive"))
      (node (ref "U11") (pin "4") (pinfunction "GND_4") (pintype "passive"))
      (node (ref "U12") (pin "4") (pinfunction "GND_4") (pintype "passive"))
      (node (ref "U13") (pin "4") (pinfunction "GND_4") (pintype "passive"))
      (node (ref "U14") (pin "11") (pinfunction "V-_11") (pintype "power_in"))
      (node (ref "U15") (pin "4") (pinfunction "GND_4") (pintype "passive"))
      (node (ref "U2") (pin "4") (pinfunction "INH_4") (pintype "passive"))
      (node (ref "U2") (pin "5") (pinfunction "GND_5") (pintype "power_in"))
      (node (ref "U3") (pin "4") (pinfunction "INH_4") (pintype "passive"))
      (node (ref "U3") (pin "5") (pinfunction "GND_5") (pintype "power_in"))
      (node (ref "U4") (pin "4") (pinfunction "GND_4") (pintype "passive"))
      (node (ref "U5") (pin "4") (pinfunction "GND_4") (pintype "passive"))
      (node (ref "U6") (pin "11") (pinfunction "V-_11") (pintype "power_in"))
      (node (ref "U7") (pin "4") (pinfunction "GND_4") (pintype "passive"))
      (node (ref "U8") (pin "4") (pinfunction "GND_4") (pintype "passive"))
      (node (ref "U9") (pin "11") (pinfunction "V-_11") (pintype "power_in"))
    )
    (net (code "28") (name "Net-(C24-Pad2)") (class "Default")
      (node (ref "C24") (pin "2") (pinfunction "2_2") (pintype "passive"))
      (node (ref "F1") (pin "2") (pinfunction "2_2") (pintype "passive"))
      (node (ref "FB1") (pin "1") (pinfunction "1_1") (pintype "passive"))
    )
    (net (code "29") (name "Net-(F1-Pad1)") (class "Default")
      (node (ref "F1") (pin "1") (pinfunction "1_1") (pintype "passive"))
      (node (ref "J4") (pin "A4/B9") (pinfunction "VBUS_A4/B9") (pintype "power_in"))
      (node (ref "J4") (pin "B4/A9") (pinfunction "VBUS_B4/A9") (pintype "power_in"))
    )
    (net (code "30") (name "Net-(J4-CC1)") (class "Default")
      (node (ref "J4") (pin "A5") (pinfunction "CC1_A5") (pintype "bidirectional"))
      (node (ref "R67") (pin "2") (pinfunction "2_2") (pintype "passive"))
    )
    (net (code "31") (name "Net-(J4-CC2)") (class "Default")
      (node (ref "J4") (pin "B5") (pinfunction "CC2_B5") (pintype "bidirectional"))
      (node (ref "R68") (pin "2") (pinfunction "2_2") (pintype "passive"))
    )
    (net (code "32") (name "Net-(M1-P1.00{slash}SWO)") (class "Default")
      (node (ref "J2") (pin "13") (pinfunction "13_13") (pintype "passive"))
      (node (ref "M1") (pin "12") (pinfunction "P1.00/SWO_12") (pintype "bidirectional"))
    )
    (net (code "33") (name "Net-(M1-SWDCLK)") (class "Default")
      (node (ref "J2") (pin "9") (pinfunction "9_9") (pintype "passive"))
      (node (ref "M1") (pin "5") (pinfunction "SWDCLK_5") (pintype "input"))
    )
    (net (code "34") (name "Net-(M1-SWDIO)") (class "Default")
      (node (ref "J2") (pin "7") (pinfunction "7_7") (pintype "passive"))
      (node (ref "M1") (pin "8") (pinfunction "SWDIO_8") (pintype "bidirectional"))
    )
    (net (code "35") (name "Net-(TP3-TP)") (class "Default")
      (node (ref "C3") (pin "1") (pinfunction "1_1") (pintype "passive"))
      (node (ref "TP3") (pin "1") (pinfunction "TP_1") (pintype "passive"))
      (node (ref "U4") (pin "1") (pinfunction "X2_1") (pintype "passive"))
    )
    (net (code "36") (name "Net-(TP4-TP)") (class "Default")
      (node (ref "C8") (pin "1") (pinfunction "1_1") (pintype "passive"))
      (node (ref "TP4") (pin "1") (pinfunction "TP_1") (pintype "passive"))
      (node (ref "U5") (pin "1") (pinfunction "X2_1") (pintype "passive"))
    )
    (net (code "37") (name "Net-(TP7-TP)") (class "Default")
      (node (ref "C16") (pin "1") (pinfunction "1_1") (pintype "passive"))
      (node (ref "TP7") (pin "1") (pinfunction "TP_1") (pintype "passive"))
      (node (ref "U7") (pin "1") (pinfunction "X2_1") (pintype "passive"))
    )
    (net (code "38") (name "Net-(TP8-TP)") (class "Default")
      (node (ref "C18") (pin "1") (pinfunction "1_1") (pintype "passive"))
      (node (ref "TP8") (pin "1") (pinfunction "TP_1") (pintype "passive"))
      (node (ref "U8") (pin "1") (pinfunction "X2_1") (pintype "passive"))
    )
    (net (code "39") (name "Net-(TP11-TP)") (class "Default")
      (node (ref "C27") (pin "1") (pinfunction "1_1") (pintype "passive"))
      (node (ref "TP11") (pin "1") (pinfunction "TP_1") (pintype "passive"))
      (node (ref "U10") (pin "1") (pinfunction "X2_1") (pintype "passive"))
    )
    (net (code "40") (name "Net-(TP12-TP)") (class "Default")
      (node (ref "C29") (pin "1") (pinfunction "1_1") (pintype "passive"))
      (node (ref "TP12") (pin "1") (pinfunction "TP_1") (pintype "passive"))
      (node (ref "U11") (pin "1") (pinfunction "X2_1") (pintype "passive"))
    )
    (net (code "41") (name "Net-(TP15-TP)") (class "Default")
      (node (ref "C37") (pin "1") (pinfunction "1_1") (pintype "passive"))
      (node (ref "TP15") (pin "1") (pinfunction "TP_1") (pintype "passive"))
      (node (ref "U12") (pin "1") (pinfunction "X2_1") (pintype "passive"))
    )
    (net (code "42") (name "Net-(TP16-TP)") (class "Default")
      (node (ref "C39") (pin "1") (pinfunction "1_1") (pintype "passive"))
      (node (ref "TP16") (pin "1") (pinfunction "TP_1") (pintype "passive"))
      (node (ref "U13") (pin "1") (pinfunction "X2_1") (pintype "passive"))
    )
    (net (code "43") (name "Net-(TP18-TP)") (class "Default")
      (node (ref "C45") (pin "1") (pinfunction "1_1") (pintype "passive"))
      (node (ref "TP18") (pin "1") (pinfunction "TP_1") (pintype "passive"))
      (node (ref "U15") (pin "1") (pinfunction "X2_1") (pintype "passive"))
    )
    (net (code "44") (name "Net-(TP19-TP)") (class "Default")
      (node (ref "TP19") (pin "1") (pinfunction "TP_1") (pintype "passive"))
      (node (ref "U1") (pin "9") (pinfunction "COM_9") (pintype "passive"))
      (node (ref "U6") (pin "12") (pinfunction "IN_D+_12") (pintype "input"))
    )
    (net (code "45") (name "Net-(TP20-TP)") (class "Default")
      (node (ref "TP20") (pin "1") (pinfunction "TP_1") (pintype "passive"))
      (node (ref "U14") (pin "12") (pinfunction "IN_D+_12") (pintype "input"))
      (node (ref "U3") (pin "9") (pinfunction "COM_9") (pintype "passive"))
    )
    (net (code "46") (name "Net-(TP21-TP)") (class "Default")
      (node (ref "TP21") (pin "1") (pinfunction "TP_1") (pintype "passive"))
      (node (ref "U2") (pin "9") (pinfunction "COM_9") (pintype "passive"))
      (node (ref "U9") (pin "12") (pinfunction "IN_D+_12") (pintype "input"))
    )
    (net (code "47") (name "Net-(U4-X1)") (class "Default")
      (node (ref "C6") (pin "1") (pinfunction "1_1") (pintype "passive"))
      (node (ref "U4") (pin "3") (pinfunction "X1_3") (pintype "passive"))
    )
    (net (code "48") (name "Net-(U5-X1)") (class "Default")
      (node (ref "C4") (pin "1") (pinfunction "1_1") (pintype "passive"))
      (node (ref "U5") (pin "3") (pinfunction "X1_3") (pintype "passive"))
    )
    (net (code "49") (name "Net-(U6A-IN_A+)") (class "Default")
      (node (ref "C1") (pin "2") (pinfunction "2_2") (pintype "passive"))
      (node (ref "C3") (pin "2") (pinfunction "2_2") (pintype "passive"))
      (node (ref "R1") (pin "1") (pinfunction "1_1") (pintype "passive"))
      (node (ref "R3") (pin "1") (pinfunction "1_1") (pintype "passive"))
      (node (ref "R8") (pin "2") (pinfunction "2_2") (pintype "passive"))
      (node (ref "U6") (pin "3") (pinfunction "IN_A+_3") (pintype "input"))
    )
    (net (code "50") (name "Net-(U6A-IN_A-)") (class "Default")
      (node (ref "C6") (pin "2") (pinfunction "2_2") (pintype "passive"))
      (node (ref "R5") (pin "1") (pinfunction "1_1") (pintype "passive"))
      (node (ref "R7") (pin "2") (pinfunction "2_2") (pintype "passive"))
      (node (ref "U6") (pin "2") (pinfunction "IN_A-_2") (pintype "input"))
    )
    (net (code "51") (name "Net-(U6B-IN_B+)") (class "Default")
      (node (ref "C2") (pin "2") (pinfunction "2_2") (pintype "passive"))
      (node (ref "C8") (pin "2") (pinfunction "2_2") (pintype "passive"))
      (node (ref "R2") (pin "1") (pinfunction "1_1") (pintype "passive"))
      (node (ref "R4") (pin "1") (pinfunction "1_1") (pintype "passive"))
      (node (ref "R9") (pin "2") (pinfunction "2_2") (pintype "passive"))
      (node (ref "U6") (pin "5") (pinfunction "IN_B+_5") (pintype "input"))
    )
    (net (code "52") (name "Net-(U6B-IN_B-)") (class "Default")
      (node (ref "C4") (pin "2") (pinfunction "2_2") (pintype "passive"))
      (node (ref "R10") (pin "2") (pinfunction "2_2") (pintype "passive"))
      (node (ref "R6") (pin "1") (pinfunction "1_1") (pintype "passive"))
      (node (ref "U6") (pin "6") (pinfunction "IN_B-_6") (pintype "input"))
    )
    (net (code "53") (name "Net-(U6C-IN_C+)") (class "Default")
      (node (ref "C11") (pin "2") (pinfunction "2_2") (pintype "passive"))
      (node (ref "C16") (pin "2") (pinfunction "2_2") (pintype "passive"))
      (node (ref "R11") (pin "1") (pinfunction "1_1") (pintype "passive"))
      (node (ref "R13") (pin "1") (pinfunction "1_1") (pintype "passive"))
      (node (ref "R17") (pin "2") (pinfunction "2_2") (pintype "passive"))
      (node (ref "U6") (pin "10") (pinfunction "IN_C+_10") (pintype "input"))
    )
    (net (code "54") (name "Net-(U6C-IN_C-)") (class "Default")
      (node (ref "C13") (pin "2") (pinfunction "2_2") (pintype "passive"))
      (node (ref "R15") (pin "1") (pinfunction "1_1") (pintype "passive"))
      (node (ref "R18") (pin "2") (pinfunction "2_2") (pintype "passive"))
      (node (ref "U6") (pin "9") (pinfunction "IN_C-_9") (pintype "input"))
    )
    (net (code "55") (name "Net-(U7-X1)") (class "Default")
      (node (ref "C13") (pin "1") (pinfunction "1_1") (pintype "passive"))
      (node (ref "U7") (pin "3") (pinfunction "X1_3") (pintype "passive"))
    )
    (net (code "56") (name "Net-(U8-X1)") (class "Default")
      (node (ref "C14") (pin "1") (pinfunction "1_1") (pintype "passive"))
      (node (ref "U8") (pin "3") (pinfunction "X1_3") (pintype "passive"))
    )
    (net (code "57") (name "Net-(U9A-IN_A+)") (class "Default")
      (node (ref "C12") (pin "2") (pinfunction "2_2") (pintype "passive"))
      (node (ref "C18") (pin "2") (pinfunction "2_2") (pintype "passive"))
      (node (ref "R12") (pin "1") (pinfunction "1_1") (pintype "passive"))
      (node (ref "R14") (pin "1") (pinfunction "1_1") (pintype "passive"))
      (node (ref "R19") (pin "2") (pinfunction "2_2") (pintype "passive"))
      (node (ref "U9") (pin "3") (pinfunction "IN_A+_3") (pintype "input"))
    )
    (net (code "58") (name "Net-(U9A-IN_A-)") (class "Default")
      (node (ref "C14") (pin "2") (pinfunction "2_2") (pintype "passive"))
      (node (ref "R16") (pin "1") (pinfunction "1_1") (pintype "passive"))
      (node (ref "R20") (pin "2") (pinfunction "2_2") (pintype "passive"))
      (node (ref "U9") (pin "2") (pinfunction "IN_A-_2") (pintype "input"))
    )
    (net (code "59") (name "Net-(U9B-IN_B+)") (class "Default")
      (node (ref "C21") (pin "2") (pinfunction "2_2") (pintype "passive"))
      (node (ref "C27") (pin "2") (pinfunction "2_2") (pintype "passive"))
      (node (ref "R21") (pin "1") (pinfunction "1_1") (pintype "passive"))
      (node (ref "R23") (pin "1") (pinfunction "1_1") (pintype "passive"))
      (node (ref "R27") (pin "2") (pinfunction "2_2") (pintype "passive"))
      (node (ref "U9") (pin "5") (pinfunction "IN_B+_5") (pintype "input"))
    )
    (net (code "60") (name "Net-(U9B-IN_B-)") (class "Default")
      (node (ref "C23") (pin "2") (pinfunction "2_2") (pintype "passive"))
      (node (ref "R25") (pin "1") (pinfunction "1_1") (pintype "passive"))
      (node (ref "R28") (pin "2") (pinfunction "2_2") (pintype "passive"))
      (node (ref "U9") (pin "6") (pinfunction "IN_B-_6") (pintype "input"))
    )
    (net (code "61") (name "Net-(U9C-IN_C+)") (class "Default")
      (node (ref "C22") (pin "2") (pinfunction "2_2") (pintype "passive"))
      (node (ref "C29") (pin "2") (pinfunction "2_2") (pintype "passive"))
      (node (ref "R22") (pin "1") (pinfunction "1_1") (pintype "passive"))
      (node (ref "R24") (pin "1") (pinfunction "1_1") (pintype "passive"))
      (node (ref "R29") (pin "2") (pinfunction "2_2") (pintype "passive"))
      (node (ref "U9") (pin "10") (pinfunction "IN_C+_10") (pintype "input"))
    )
    (net (code "62") (name "Net-(U9C-IN_C-)") (class "Default")
      (node (ref "C25") (pin "2") (pinfunction "2_2") (pintype "passive"))
      (node (ref "R26") (pin "1") (pinfunction "1_1") (pintype "passive"))
      (node (ref "R30") (pin "2") (pinfunction "2_2") (pintype "passive"))
      (node (ref "U9") (pin "9") (pinfunction "IN_C-_9") (pintype "input"))
    )
    (net (code "63") (name "Net-(U10-X1)") (class "Default")
      (node (ref "C23") (pin "1") (pinfunction "1_1") (pintype "passive"))
      (node (ref "U10") (pin "3") (pinfunction "X1_3") (pintype "passive"))
    )
    (net (code "64") (name "Net-(U11-X1)") (class "Default")
      (node (ref "C25") (pin "1") (pinfunction "1_1") (pintype "passive"))
      (node (ref "U11") (pin "3") (pinfunction "X1_3") (pintype "passive"))
    )
    (net (code "65") (name "Net-(U12-X1)") (class "Default")
      (node (ref "C34") (pin "1") (pinfunction "1_1") (pintype "passive"))
      (node (ref "U12") (pin "3") (pinfunction "X1_3") (pintype "passive"))
    )
    (net (code "66") (name "Net-(U13-X1)") (class "Default")
      (node (ref "C35") (pin "1") (pinfunction "1_1") (pintype "passive"))
      (node (ref "U13") (pin "3") (pinfunction "X1_3") (pintype "passive"))
    )
    (net (code "67") (name "Net-(U14A-IN_A+)") (class "Default")
      (node (ref "C32") (pin "2") (pinfunction "2_2") (pintype "passive"))
      (node (ref "C37") (pin "2") (pinfunction "2_2") (pintype "passive"))
      (node (ref "R31") (pin "1") (pinfunction "1_1") (pintype "passive"))
      (node (ref "R33") (pin "1") (pinfunction "1_1") (pintype "passive"))
      (node (ref "R37") (pin "2") (pinfunction "2_2") (pintype "passive"))
      (node (ref "U14") (pin "3") (pinfunction "IN_A+_3") (pintype "input"))
    )
    (net (code "68") (name "Net-(U14A-IN_A-)") (class "Default")
      (node (ref "C34") (pin "2") (pinfunction "2_2") (pintype "passive"))
      (node (ref "R35") (pin "1") (pinfunction "1_1") (pintype "passive"))
      (node (ref "R38") (pin "2") (pinfunction "2_2") (pintype "passive"))
      (node (ref "U14") (pin "2") (pinfunction "IN_A-_2") (pintype "input"))
    )
    (net (code "69") (name "Net-(U14B-IN_B+)") (class "Default")
      (node (ref "C33") (pin "2") (pinfunction "2_2") (pintype "passive"))
      (node (ref "C39") (pin "2") (pinfunction "2_2") (pintype "passive"))
      (node (ref "R32") (pin "1") (pinfunction "1_1") (pintype "passive"))
      (node (ref "R34") (pin "1") (pinfunction "1_1") (pintype "passive"))
      (node (ref "R39") (pin "2") (pinfunction "2_2") (pintype "passive"))
      (node (ref "U14") (pin "5") (pinfunction "IN_B+_5") (pintype "input"))
    )
    (net (code "70") (name "Net-(U14B-IN_B-)") (class "Default")
      (node (ref "C35") (pin "2") (pinfunction "2_2") (pintype "passive"))
      (node (ref "R36") (pin "1") (pinfunction "1_1") (pintype "passive"))
      (node (ref "R40") (pin "2") (pinfunction "2_2") (pintype "passive"))
      (node (ref "U14") (pin "6") (pinfunction "IN_B-_6") (pintype "input"))
    )
    (net (code "71") (name "Net-(U14C-IN_C+)") (class "Default")
      (node (ref "C42") (pin "2") (pinfunction "2_2") (pintype "passive"))
      (node (ref "C45") (pin "2") (pinfunction "2_2") (pintype "passive"))
      (node (ref "R41") (pin "1") (pinfunction "1_1") (pintype "passive"))
      (node (ref "R42") (pin "1") (pinfunction "1_1") (pintype "passive"))
      (node (ref "R44") (pin "2") (pinfunction "2_2") (pintype "passive"))
      (node (ref "U14") (pin "10") (pinfunction "IN_C+_10") (pintype "input"))
    )
    (net (code "72") (name "Net-(U14C-IN_C-)") (class "Default")
      (node (ref "C43") (pin "2") (pinfunction "2_2") (pintype "passive"))
      (node (ref "R43") (pin "1") (pinfunction "1_1") (pintype "passive"))
      (node (ref "R45") (pin "2") (pinfunction "2_2") (pintype "passive"))
      (node (ref "U14") (pin "9") (pinfunction "IN_C-_9") (pintype "input"))
    )
    (net (code "73") (name "Net-(U15-X1)") (class "Default")
      (node (ref "C43") (pin "1") (pinfunction "1_1") (pintype "passive"))
      (node (ref "U15") (pin "3") (pinfunction "X1_3") (pintype "passive"))
    )
    (net (code "74") (name "VBUS") (class "Default")
      (node (ref "C1") (pin "1") (pinfunction "1_1") (pintype "passive"))
      (node (ref "C11") (pin "1") (pinfunction "1_1") (pintype "passive"))
      (node (ref "C12") (pin "1") (pinfunction "1_1") (pintype "passive"))
      (node (ref "C15") (pin "2") (pinfunction "2_2") (pintype "passive"))
      (node (ref "C17") (pin "2") (pinfunction "2_2") (pintype "passive"))
      (node (ref "C2") (pin "1") (pinfunction "1_1") (pintype "passive"))
      (node (ref "C20") (pin "1") (pinfunction "1_1") (pintype "passive"))
      (node (ref "C21") (pin "1") (pinfunction "1_1") (pintype "passive"))
      (node (ref "C22") (pin "1") (pinfunction "1_1") (pintype "passive"))
      (node (ref "C26") (pin "2") (pinfunction "2_2") (pintype "passive"))
      (node (ref "C28") (pin "2") (pinfunction "2_2") (pintype "passive"))
      (node (ref "C32") (pin "1") (pinfunction "1_1") (pintype "passive"))
      (node (ref "C33") (pin "1") (pinfunction "1_1") (pintype "passive"))
      (node (ref "C36") (pin "2") (pinfunction "2_2") (pintype "passive"))
      (node (ref "C38") (pin "2") (pinfunction "2_2") (pintype "passive"))
      (node (ref "C40") (pin "1") (pinfunction "1_1") (pintype "passive"))
      (node (ref "C42") (pin "1") (pinfunction "1_1") (pintype "passive"))
      (node (ref "C44") (pin "2") (pinfunction "2_2") (pintype "passive"))
      (node (ref "C5") (pin "2") (pinfunction "2_2") (pintype "passive"))
      (node (ref "C7") (pin "2") (pinfunction "2_2") (pintype "passive"))
      (node (ref "C9") (pin "1") (pinfunction "1_1") (pintype "passive"))
      (node (ref "FB1") (pin "2") (pinfunction "2_2") (pintype "passive"))
      (node (ref "J1") (pin "2") (pinfunction "2_2") (pintype "passive"))
      (node (ref "J2") (pin "19") (pinfunction "19_19") (pintype "passive"))
      (node (ref "J3") (pin "1") (pinfunction "1_1") (pintype "passive"))
      (node (ref "M1") (pin "23") (pinfunction "VDDH_23") (pintype "power_in"))
      (node (ref "M1") (pin "24") (pinfunction "VBUS_24") (pintype "power_in"))
      (node (ref "P3") (pin "1") (pinfunction "1_1") (pintype "passive"))
      (node (ref "P7") (pin "1") (pinfunction "1_1") (pintype "passive"))
      (node (ref "R1") (pin "2") (pinfunction "2_2") (pintype "passive"))
      (node (ref "R11") (pin "2") (pinfunction "2_2") (pintype "passive"))
      (node (ref "R12") (pin "2") (pinfunction "2_2") (pintype "passive"))
      (node (ref "R2") (pin "2") (pinfunction "2_2") (pintype "passive"))
      (node (ref "R21") (pin "2") (pinfunction "2_2") (pintype "passive"))
      (node (ref "R22") (pin "2") (pinfunction "2_2") (pintype "passive"))
      (node (ref "R31") (pin "2") (pinfunction "2_2") (pintype "passive"))
      (node (ref "R32") (pin "2") (pinfunction "2_2") (pintype "passive"))
      (node (ref "R41") (pin "2") (pinfunction "2_2") (pintype "passive"))
      (node (ref "TP22") (pin "1") (pinfunction "TP_1") (pintype "passive"))
      (node (ref "U1") (pin "10") (pinfunction "V+_10") (pintype "power_in"))
      (node (ref "U10") (pin "6") (pinfunction "VDD_6") (pintype "passive"))
      (node (ref "U11") (pin "6") (pinfunction "VDD_6") (pintype "passive"))
      (node (ref "U12") (pin "6") (pinfunction "VDD_6") (pintype "passive"))
      (node (ref "U13") (pin "6") (pinfunction "VDD_6") (pintype "passive"))
      (node (ref "U14") (pin "4") (pinfunction "V+_4") (pintype "power_in"))
      (node (ref "U15") (pin "6") (pinfunction "VDD_6") (pintype "passive"))
      (node (ref "U2") (pin "10") (pinfunction "V+_10") (pintype "power_in"))
      (node (ref "U3") (pin "10") (pinfunction "V+_10") (pintype "power_in"))
      (node (ref "U4") (pin "6") (pinfunction "VDD_6") (pintype "passive"))
      (node (ref "U5") (pin "6") (pinfunction "VDD_6") (pintype "passive"))
      (node (ref "U6") (pin "4") (pinfunction "V+_4") (pintype "power_in"))
      (node (ref "U7") (pin "6") (pinfunction "VDD_6") (pintype "passive"))
      (node (ref "U8") (pin "6") (pinfunction "VDD_6") (pintype "passive"))
      (node (ref "U9") (pin "4") (pinfunction "V+_4") (pintype "power_in"))
    )
    (net (code "75") (name "VDD_NRF") (class "Default")
      (node (ref "J2") (pin "1") (pinfunction "1_1") (pintype "passive"))
      (node (ref "J2") (pin "2") (pinfunction "2_2") (pintype "passive"))
      (node (ref "M1") (pin "22") (pinfunction "VDD_NRF_22") (pintype "passive"))
      (node (ref "TP23") (pin "1") (pinfunction "TP_1") (pintype "passive"))
    )
    (net (code "76") (name "unconnected-(J2-Pad3)") (class "Default")
      (node (ref "J2") (pin "3") (pinfunction "3_3") (pintype "passive+no_connect"))
    )
    (net (code "77") (name "unconnected-(J2-Pad5)") (class "Default")
      (node (ref "J2") (pin "5") (pinfunction "5_5") (pintype "passive+no_connect"))
    )
    (net (code "78") (name "unconnected-(J2-Pad11)") (class "Default")
      (node (ref "J2") (pin "11") (pinfunction "11_11") (pintype "passive+no_connect"))
    )
    (net (code "79") (name "unconnected-(J2-Pad17)") (class "Default")
      (node (ref "J2") (pin "17") (pinfunction "17_17") (pintype "passive+no_connect"))
    )
    (net (code "80") (name "unconnected-(J4-SBU1-PadA8)") (class "Default")
      (node (ref "J4") (pin "A8") (pinfunction "SBU1_A8") (pintype "bidirectional+no_connect"))
    )
    (net (code "81") (name "unconnected-(J4-SBU2-PadB8)") (class "Default")
      (node (ref "J4") (pin "B8") (pinfunction "SBU2_B8") (pintype "bidirectional+no_connect"))
    )
    (net (code "82") (name "unconnected-(M1-P0.04{slash}AIN2-Pad37)") (class "Default")
      (node (ref "M1") (pin "37") (pinfunction "P0.04/AIN2_37") (pintype "bidirectional"))
    )
    (net (code "83") (name "unconnected-(M1-P0.05{slash}AIN3-Pad36)") (class "Default")
      (node (ref "M1") (pin "36") (pinfunction "P0.05/AIN3_36") (pintype "bidirectional"))
    )
    (net (code "84") (name "unconnected-(M1-P0.08-Pad33)") (class "Default")
      (node (ref "M1") (pin "33") (pinfunction "P0.08_33") (pintype "bidirectional"))
    )
    (net (code "85") (name "unconnected-(M1-P0.09{slash}NFC1-Pad54)") (class "Default")
      (node (ref "M1") (pin "54") (pinfunction "P0.09/NFC1_54") (pintype "bidirectional"))
    )
    (net (code "86") (name "unconnected-(M1-P0.10{slash}NFC2-Pad53)") (class "Default")
      (node (ref "M1") (pin "53") (pinfunction "P0.10/NFC2_53") (pintype "bidirectional"))
    )
    (net (code "87") (name "unconnected-(M1-P0.11-Pad30)") (class "Default")
      (node (ref "M1") (pin "30") (pinfunction "P0.11_30") (pintype "bidirectional"))
    )
    (net (code "88") (name "unconnected-(M1-P0.12-Pad29)") (class "Default")
      (node (ref "M1") (pin "29") (pinfunction "P0.12_29") (pintype "bidirectional"))
    )
    (net (code "89") (name "unconnected-(M1-P0.15-Pad26)") (class "Default")
      (node (ref "M1") (pin "26") (pinfunction "P0.15_26") (pintype "bidirectional"))
    )
    (net (code "90") (name "unconnected-(M1-P0.16-Pad25)") (class "Default")
      (node (ref "M1") (pin "25") (pinfunction "P0.16_25") (pintype "bidirectional"))
    )
    (net (code "91") (name "unconnected-(M1-P0.19-Pad11)") (class "Default")
      (node (ref "M1") (pin "11") (pinfunction "P0.19_11") (pintype "bidirectional"))
    )
    (net (code "92") (name "unconnected-(M1-P0.21-Pad14)") (class "Default")
      (node (ref "M1") (pin "14") (pinfunction "P0.21_14") (pintype "bidirectional"))
    )
    (net (code "93") (name "unconnected-(M1-P0.22-Pad10)") (class "Default")
      (node (ref "M1") (pin "10") (pinfunction "P0.22_10") (pintype "bidirectional"))
    )
    (net (code "94") (name "unconnected-(M1-P0.23-Pad16)") (class "Default")
      (node (ref "M1") (pin "16") (pinfunction "P0.23_16") (pintype "bidirectional"))
    )
    (net (code "95") (name "unconnected-(M1-P0.24-Pad15)") (class "Default")
      (node (ref "M1") (pin "15") (pinfunction "P0.24_15") (pintype "bidirectional"))
    )
    (net (code "96") (name "unconnected-(M1-P0.25-Pad9)") (class "Default")
      (node (ref "M1") (pin "9") (pinfunction "P0.25_9") (pintype "bidirectional"))
    )
    (net (code "97") (name "unconnected-(M1-P0.26-Pad39)") (class "Default")
      (node (ref "M1") (pin "39") (pinfunction "P0.26_39") (pintype "bidirectional"))
    )
    (net (code "98") (name "unconnected-(M1-P0.27-Pad38)") (class "Default")
      (node (ref "M1") (pin "38") (pinfunction "P0.27_38") (pintype "bidirectional"))
    )
    (net (code "99") (name "unconnected-(M1-P1.01-Pad7)") (class "Default")
      (node (ref "M1") (pin "7") (pinfunction "P1.01_7") (pintype "bidirectional"))
    )
    (net (code "100") (name "unconnected-(M1-P1.02-Pad3)") (class "Default")
      (node (ref "M1") (pin "3") (pinfunction "P1.02_3") (pintype "bidirectional"))
    )
    (net (code "101") (name "unconnected-(M1-P1.03-Pad2)") (class "Default")
      (node (ref "M1") (pin "2") (pinfunction "P1.03_2") (pintype "bidirectional"))
    )
    (net (code "102") (name "unconnected-(M1-P1.04-Pad6)") (class "Default")
      (node (ref "M1") (pin "6") (pinfunction "P1.04_6") (pintype "bidirectional"))
    )
    (net (code "103") (name "unconnected-(M1-P1.05-Pad4)") (class "Default")
      (node (ref "M1") (pin "4") (pinfunction "P1.05_4") (pintype "bidirectional"))
    )
    (net (code "104") (name "unconnected-(M1-P1.06-Pad52)") (class "Default")
      (node (ref "M1") (pin "52") (pinfunction "P1.06_52") (pintype "bidirectional"))
    )
    (net (code "105") (name "unconnected-(M1-P1.07-Pad1)") (class "Default")
      (node (ref "M1") (pin "1") (pinfunction "P1.07_1") (pintype "bidirectional"))
    )
    (net (code "106") (name "unconnected-(M1-P1.08-Pad32)") (class "Default")
      (node (ref "M1") (pin "32") (pinfunction "P1.08_32") (pintype "bidirectional"))
    )
    (net (code "107") (name "unconnected-(M1-P1.09-Pad31)") (class "Default")
      (node (ref "M1") (pin "31") (pinfunction "P1.09_31") (pintype "bidirectional"))
    )
    (net (code "108") (name "unconnected-(M1-P1.10-Pad51)") (class "Default")
      (node (ref "M1") (pin "51") (pinfunction "P1.10_51") (pintype "bidirectional"))
    )
    (net (code "109") (name "unconnected-(M1-P1.11-Pad50)") (class "Default")
      (node (ref "M1") (pin "50") (pinfunction "P1.11_50") (pintype "bidirectional"))
    )
    (net (code "110") (name "unconnected-(M1-P1.12-Pad49)") (class "Default")
      (node (ref "M1") (pin "49") (pinfunction "P1.12_49") (pintype "bidirectional"))
    )
    (net (code "111") (name "unconnected-(M1-P1.13-Pad48)") (class "Default")
      (node (ref "M1") (pin "48") (pinfunction "P1.13_48") (pintype "bidirectional"))
    )
    (net (code "112") (name "unconnected-(M1-P1.14-Pad47)") (class "Default")
      (node (ref "M1") (pin "47") (pinfunction "P1.14_47") (pintype "bidirectional"))
    )
    (net (code "113") (name "unconnected-(M1-P1.15-Pad46)") (class "Default")
      (node (ref "M1") (pin "46") (pinfunction "P1.15_46") (pintype "bidirectional"))
    )
    (net (code "114") (name "unconnected-(U1-NO3-Pad2)") (class "Default")
      (node (ref "U1") (pin "2") (pinfunction "NO3_2") (pintype "passive+no_connect"))
    )
    (net (code "115") (name "unconnected-(U2-NO3-Pad2)") (class "Default")
      (node (ref "U2") (pin "2") (pinfunction "NO3_2") (pintype "passive+no_connect"))
    )
    (net (code "116") (name "unconnected-(U3-NO3-Pad2)") (class "Default")
      (node (ref "U3") (pin "2") (pinfunction "NO3_2") (pintype "passive+no_connect"))
    )
    (net (code "117") (name "unconnected-(U4-NC-Pad2)") (class "Default")
      (node (ref "U4") (pin "2") (pinfunction "NC_2") (pintype "passive"))
    )
    (net (code "118") (name "unconnected-(U4-NC-Pad5)") (class "Default")
      (node (ref "U4") (pin "5") (pinfunction "NC_5") (pintype "passive"))
    )
    (net (code "119") (name "unconnected-(U5-NC-Pad2)") (class "Default")
      (node (ref "U5") (pin "2") (pinfunction "NC_2") (pintype "passive"))
    )
    (net (code "120") (name "unconnected-(U5-NC-Pad5)") (class "Default")
      (node (ref "U5") (pin "5") (pinfunction "NC_5") (pintype "passive"))
    )
    (net (code "121") (name "unconnected-(U7-NC-Pad2)") (class "Default")
      (node (ref "U7") (pin "2") (pinfunction "NC_2") (pintype "passive"))
    )
    (net (code "122") (name "unconnected-(U7-NC-Pad5)") (class "Default")
      (node (ref "U7") (pin "5") (pinfunction "NC_5") (pintype "passive"))
    )
    (net (code "123") (name "unconnected-(U8-NC-Pad2)") (class "Default")
      (node (ref "U8") (pin "2") (pinfunction "NC_2") (pintype "passive"))
    )
    (net (code "124") (name "unconnected-(U8-NC-Pad5)") (class "Default")
      (node (ref "U8") (pin "5") (pinfunction "NC_5") (pintype "passive"))
    )
    (net (code "125") (name "unconnected-(U10-NC-Pad2)") (class "Default")
      (node (ref "U10") (pin "2") (pinfunction "NC_2") (pintype "passive"))
    )
    (net (code "126") (name "unconnected-(U10-NC-Pad5)") (class "Default")
      (node (ref "U10") (pin "5") (pinfunction "NC_5") (pintype "passive"))
    )
    (net (code "127") (name "unconnected-(U11-NC-Pad2)") (class "Default")
      (node (ref "U11") (pin "2") (pinfunction "NC_2") (pintype "passive"))
    )
    (net (code "128") (name "unconnected-(U11-NC-Pad5)") (class "Default")
      (node (ref "U11") (pin "5") (pinfunction "NC_5") (pintype "passive"))
    )
    (net (code "129") (name "unconnected-(U12-NC-Pad2)") (class "Default")
      (node (ref "U12") (pin "2") (pinfunction "NC_2") (pintype "passive"))
    )
    (net (code "130") (name "unconnected-(U12-NC-Pad5)") (class "Default")
      (node (ref "U12") (pin "5") (pinfunction "NC_5") (pintype "passive"))
    )
    (net (code "131") (name "unconnected-(U13-NC-Pad2)") (class "Default")
      (node (ref "U13") (pin "2") (pinfunction "NC_2") (pintype "passive"))
    )
    (net (code "132") (name "unconnected-(U13-NC-Pad5)") (class "Default")
      (node (ref "U13") (pin "5") (pinfunction "NC_5") (pintype "passive"))
    )
    (net (code "133") (name "unconnected-(U15-NC-Pad2)") (class "Default")
      (node (ref "U15") (pin "2") (pinfunction "NC_2") (pintype "passive"))
    )
    (net (code "134") (name "unconnected-(U15-NC-Pad5)") (class "Default")
      (node (ref "U15") (pin "5") (pinfunction "NC_5") (pintype "passive"))
    )
  )
)
